# GEVCU-5_1.net
KiCad netlist of a schematic drawn in EAGLE
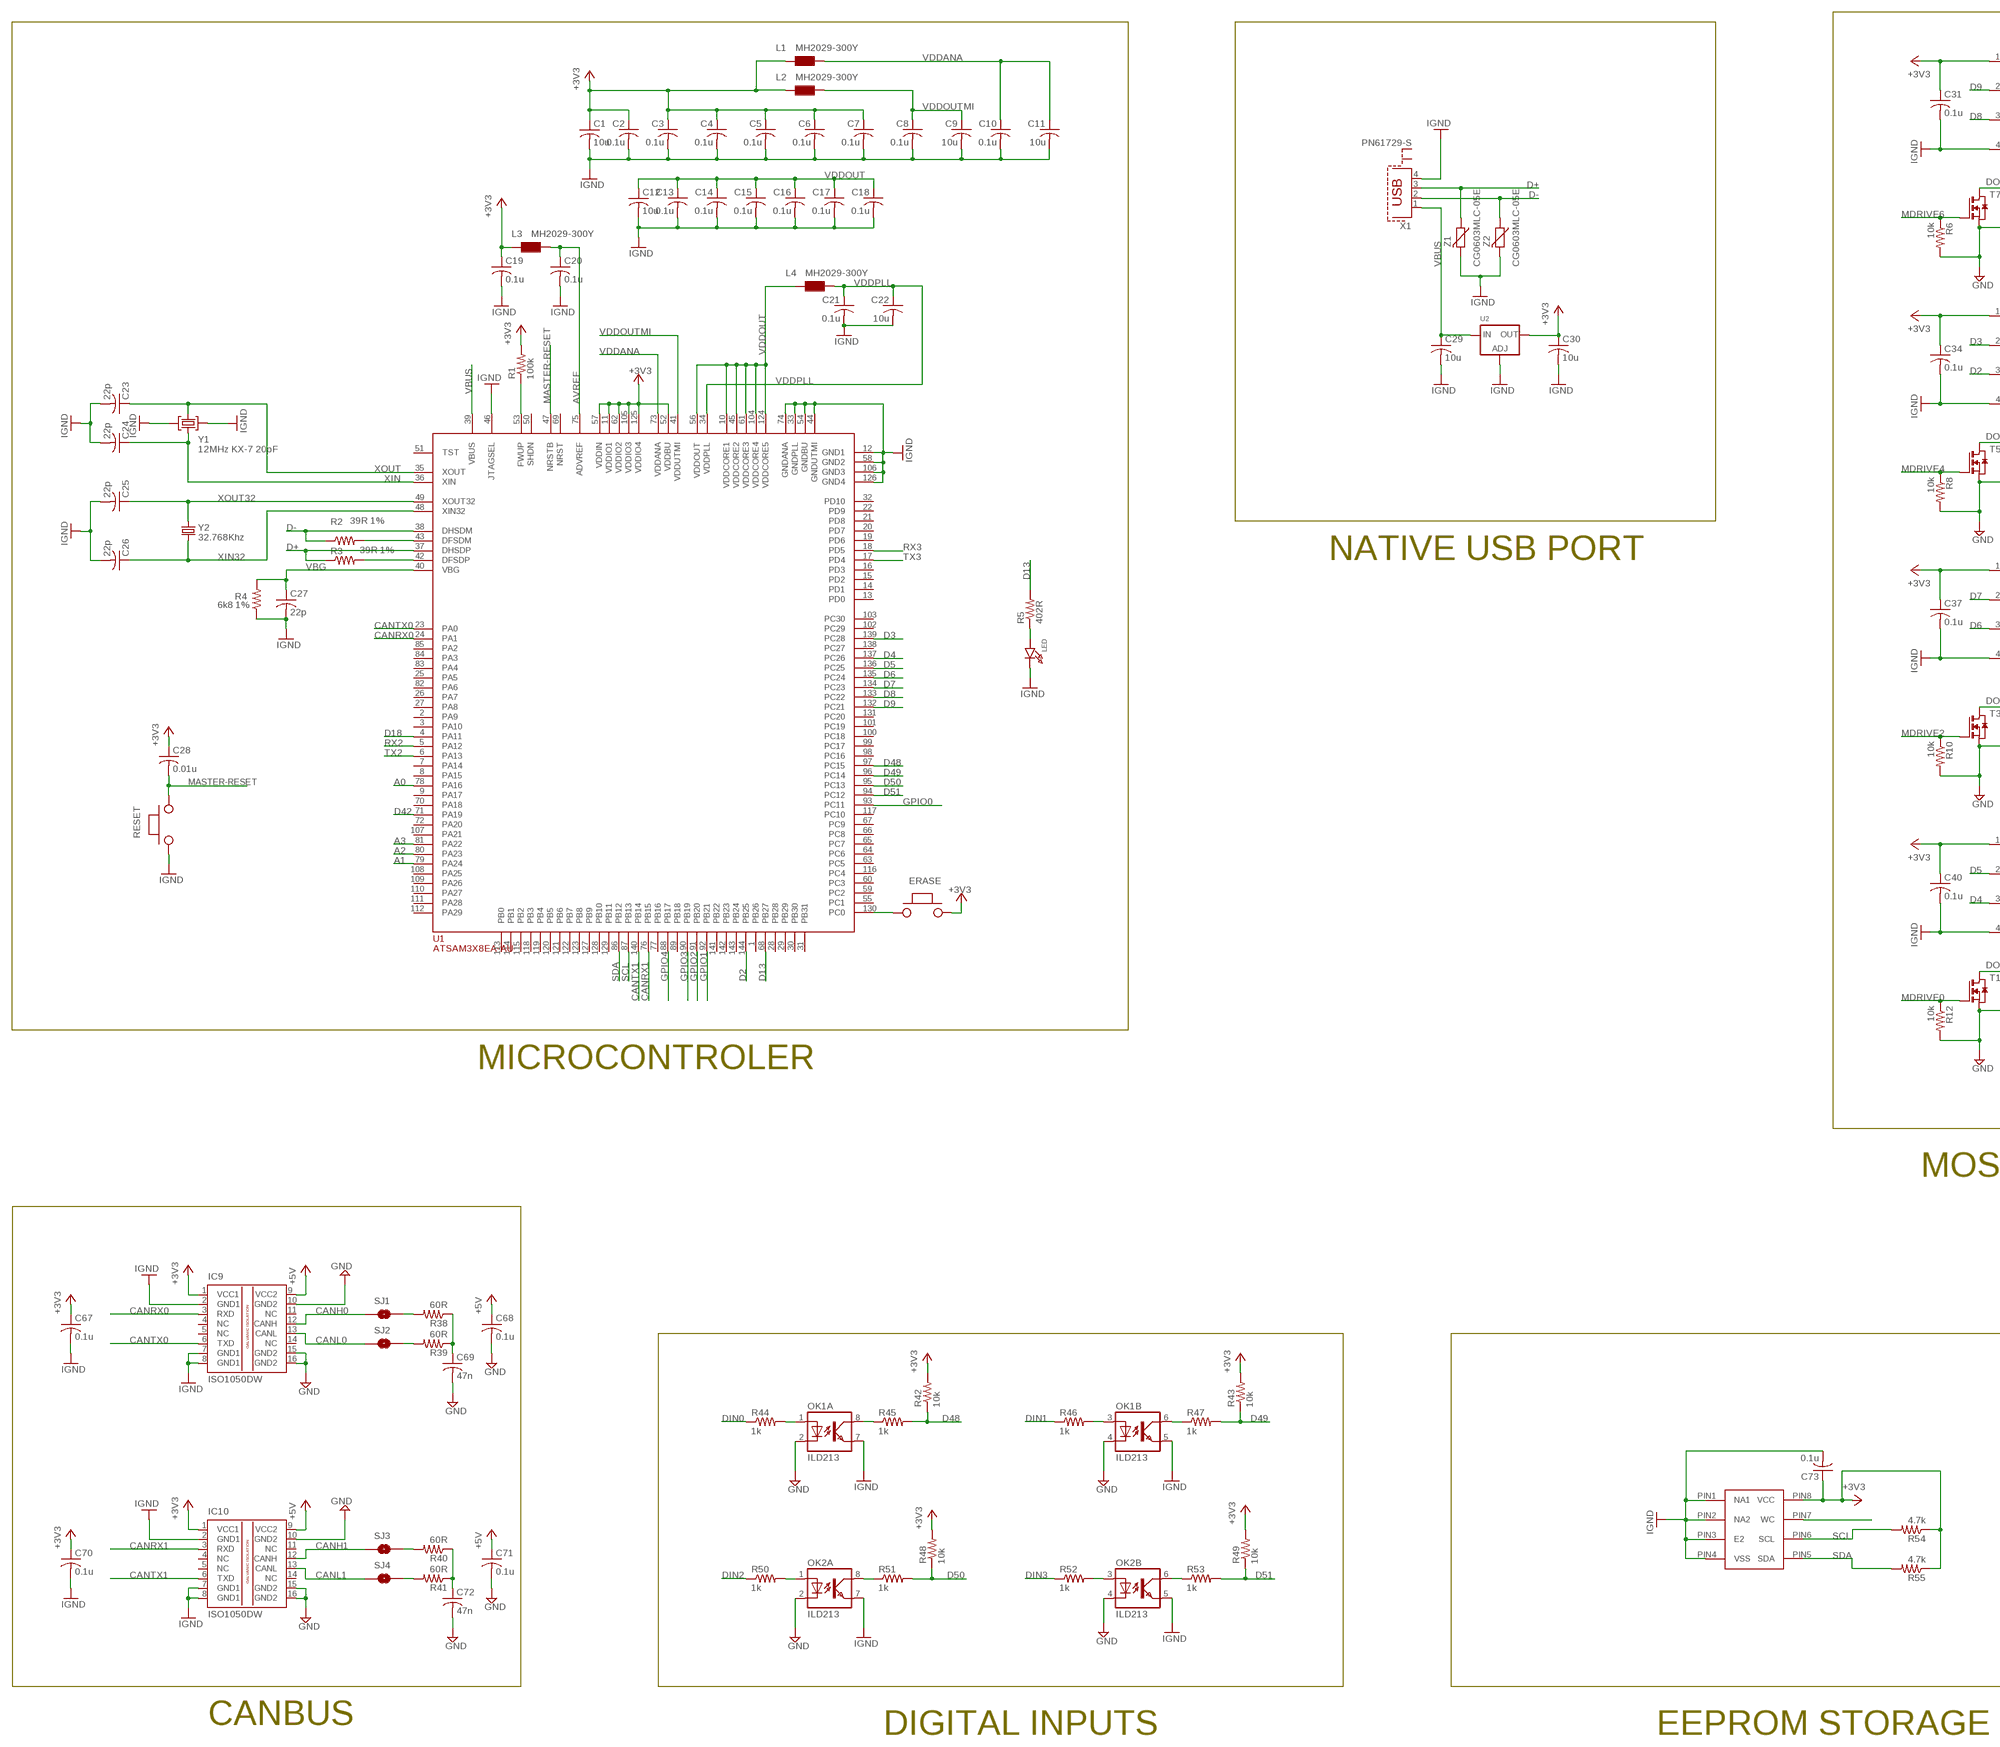
[diagram p0: schematic, sheet 1, part 1 of 2]
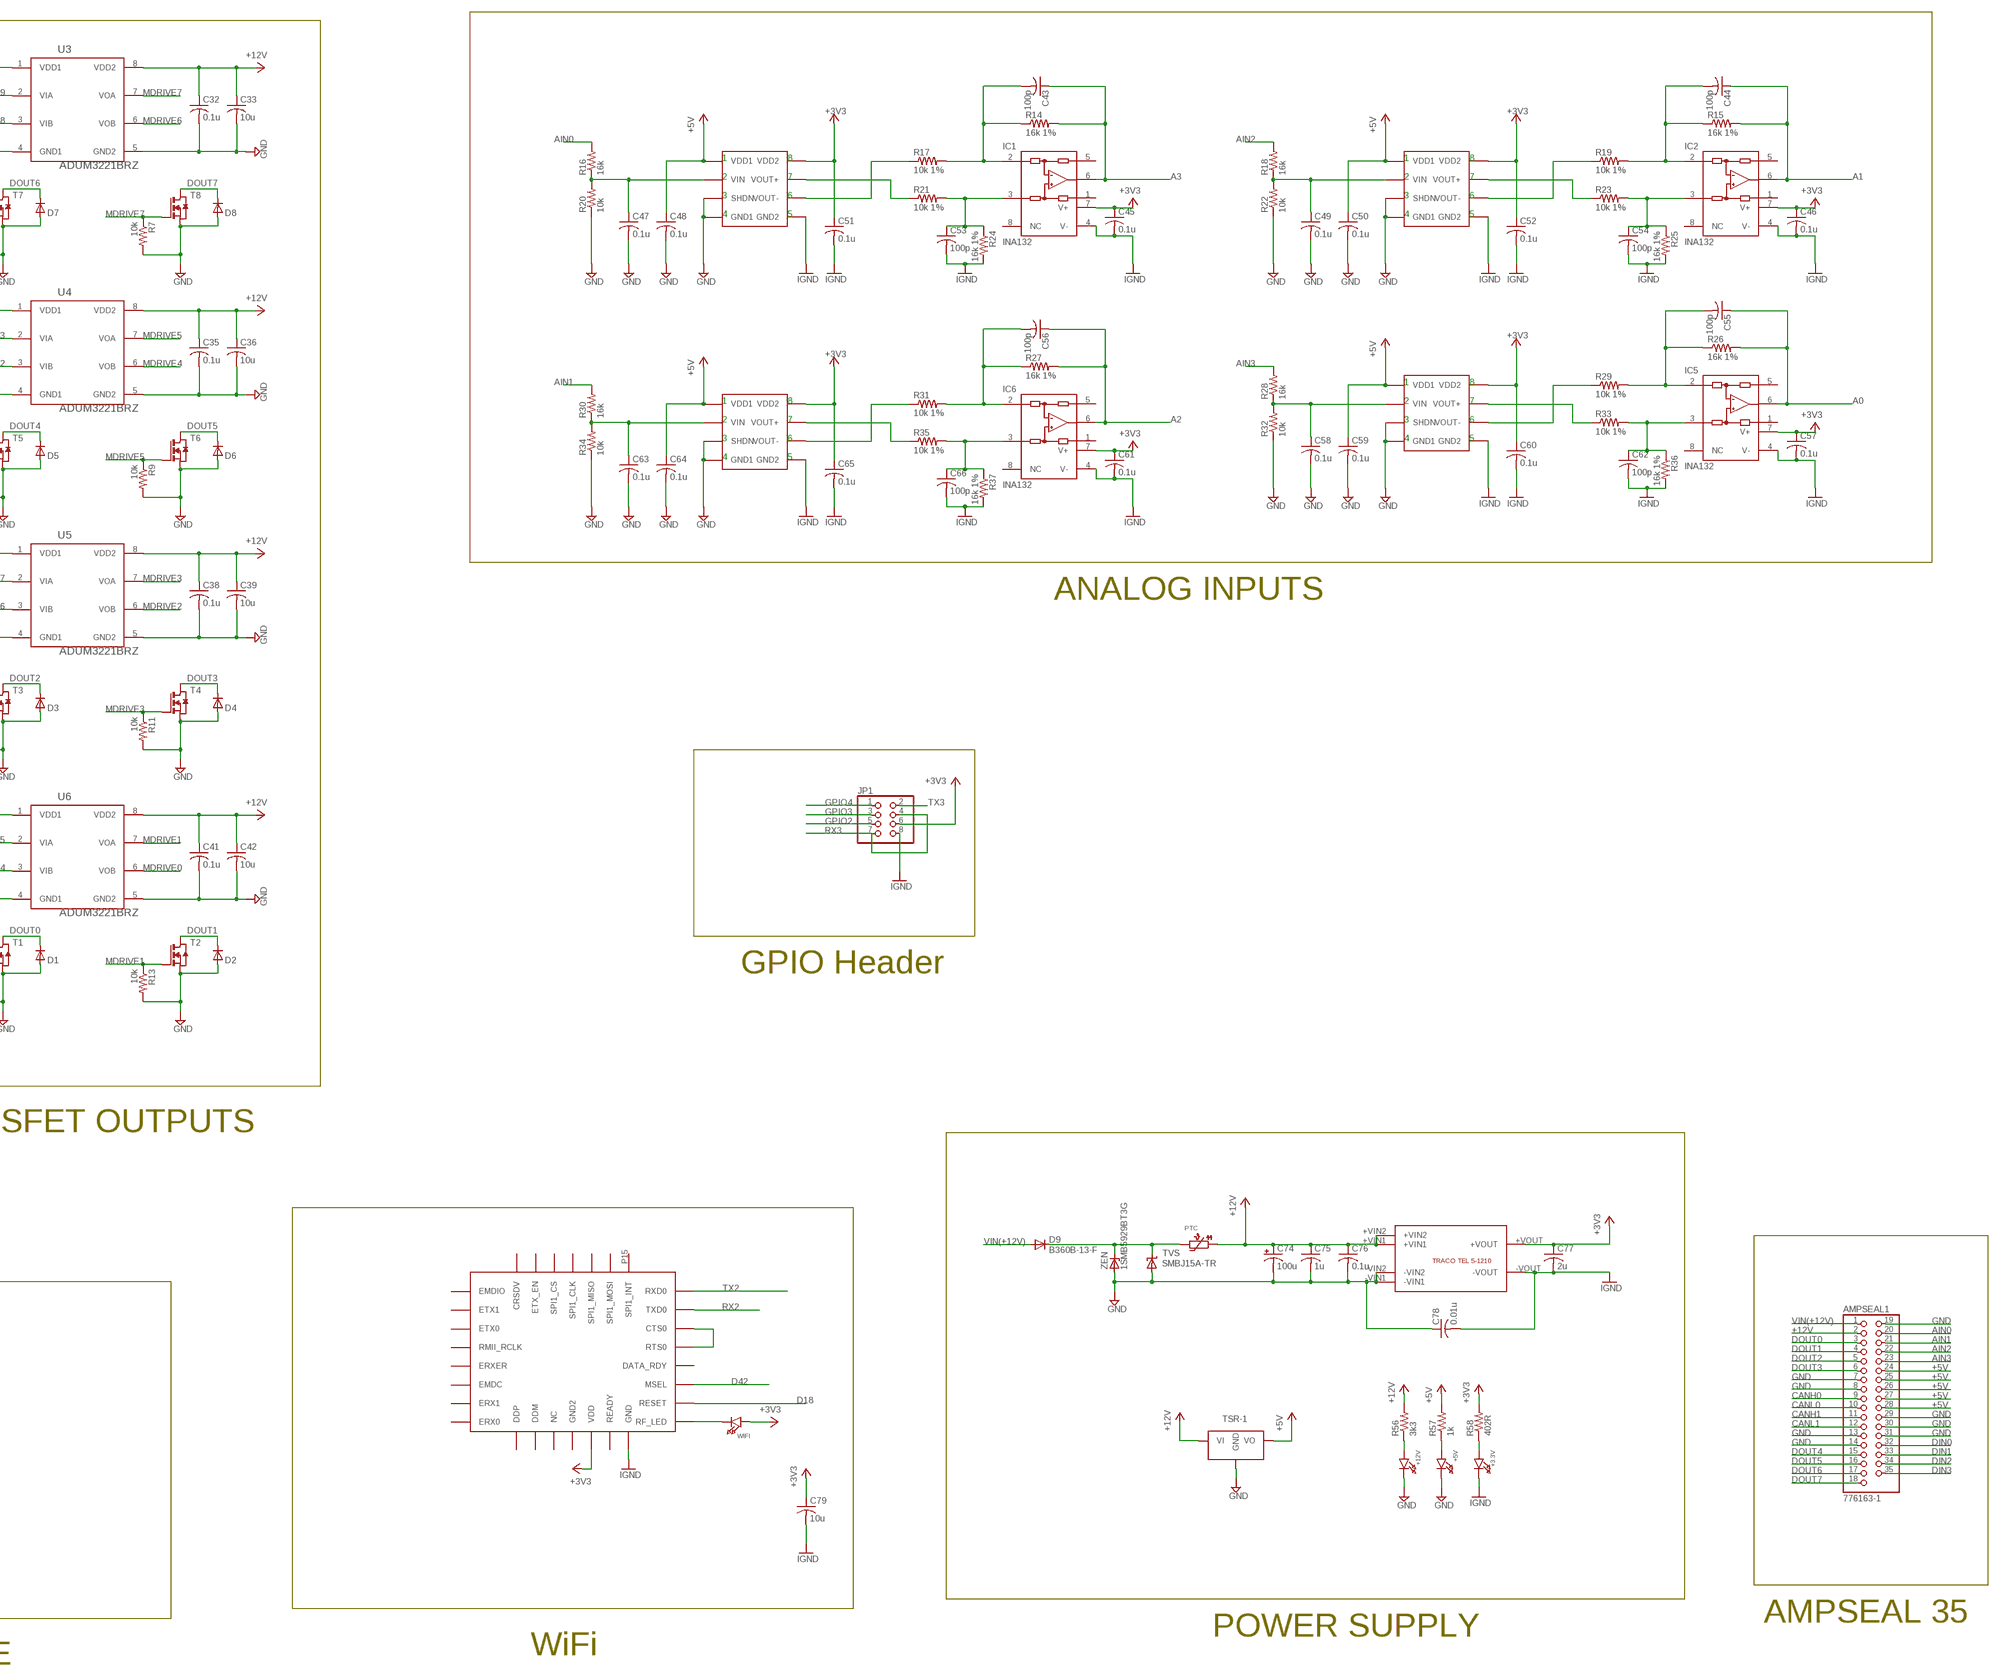
[diagram p1: schematic, sheet 1, part 2 of 2]

(export (version "E")
  (design (tool "Eeschema 10.0.6"))
  (components
    (comp (ref "+3.3V")
      (value "LED0805")
      (footprint "eagle-import:CHIPLED_0805")
      (libsource (lib "eagle-import") (part "LED0805"))
    )
    (comp (ref "+5V")
      (value "LED0805")
      (footprint "eagle-import:CHIPLED_0805")
      (libsource (lib "eagle-import") (part "LED0805"))
    )
    (comp (ref "+12V")
      (value "LED0805")
      (footprint "eagle-import:CHIPLED_0805")
      (libsource (lib "eagle-import") (part "LED0805"))
    )
    (comp (ref "AMPSEAL1")
      (value "776163-1")
      (footprint "eagle-import:AMPSEAL35")
      (libsource (lib "eagle-import") (part "AMPSEAL35"))
    )
    (comp (ref "C1")
      (value "10u")
      (footprint "eagle-import:C0805")
      (libsource (lib "eagle-import") (part "C-USC0805"))
    )
    (comp (ref "C2")
      (value "0.1u")
      (footprint "eagle-import:C0805")
      (libsource (lib "eagle-import") (part "C-USC0805"))
    )
    (comp (ref "C3")
      (value "0.1u")
      (footprint "eagle-import:C0805")
      (libsource (lib "eagle-import") (part "C-USC0805"))
    )
    (comp (ref "C4")
      (value "0.1u")
      (footprint "eagle-import:C0805")
      (libsource (lib "eagle-import") (part "C-USC0805"))
    )
    (comp (ref "C5")
      (value "0.1u")
      (footprint "eagle-import:C0805")
      (libsource (lib "eagle-import") (part "C-USC0805"))
    )
    (comp (ref "C6")
      (value "0.1u")
      (footprint "eagle-import:C0805")
      (libsource (lib "eagle-import") (part "C-USC0805"))
    )
    (comp (ref "C7")
      (value "0.1u")
      (footprint "eagle-import:C0805")
      (libsource (lib "eagle-import") (part "C-USC0805"))
    )
    (comp (ref "C8")
      (value "0.1u")
      (footprint "eagle-import:C0805")
      (libsource (lib "eagle-import") (part "C-USC0805"))
    )
    (comp (ref "C9")
      (value "10u")
      (footprint "eagle-import:C0805")
      (libsource (lib "eagle-import") (part "C-USC0805"))
    )
    (comp (ref "C10")
      (value "0.1u")
      (footprint "eagle-import:C0805")
      (libsource (lib "eagle-import") (part "C-USC0805"))
    )
    (comp (ref "C11")
      (value "10u")
      (footprint "eagle-import:C0805")
      (libsource (lib "eagle-import") (part "C-USC0805"))
    )
    (comp (ref "C12")
      (value "10u")
      (footprint "eagle-import:C0805")
      (libsource (lib "eagle-import") (part "C-USC0805"))
    )
    (comp (ref "C13")
      (value "0.1u")
      (footprint "eagle-import:C0805")
      (libsource (lib "eagle-import") (part "C-USC0805"))
    )
    (comp (ref "C14")
      (value "0.1u")
      (footprint "eagle-import:C0805")
      (libsource (lib "eagle-import") (part "C-USC0805"))
    )
    (comp (ref "C15")
      (value "0.1u")
      (footprint "eagle-import:C0805")
      (libsource (lib "eagle-import") (part "C-USC0805"))
    )
    (comp (ref "C16")
      (value "0.1u")
      (footprint "eagle-import:C0805")
      (libsource (lib "eagle-import") (part "C-USC0805"))
    )
    (comp (ref "C17")
      (value "0.1u")
      (footprint "eagle-import:C0805")
      (libsource (lib "eagle-import") (part "C-USC0805"))
    )
    (comp (ref "C18")
      (value "0.1u")
      (footprint "eagle-import:C0805")
      (libsource (lib "eagle-import") (part "C-USC0805"))
    )
    (comp (ref "C19")
      (value "0.1u")
      (footprint "eagle-import:C0805")
      (libsource (lib "eagle-import") (part "C-USC0805"))
    )
    (comp (ref "C20")
      (value "0.1u")
      (footprint "eagle-import:C0805")
      (libsource (lib "eagle-import") (part "C-USC0805"))
    )
    (comp (ref "C21")
      (value "0.1u")
      (footprint "eagle-import:C0805")
      (libsource (lib "eagle-import") (part "C-USC0805"))
    )
    (comp (ref "C22")
      (value "10u")
      (footprint "eagle-import:C0805")
      (libsource (lib "eagle-import") (part "C-USC0805"))
    )
    (comp (ref "C23")
      (value "22p")
      (footprint "eagle-import:C1206")
      (libsource (lib "eagle-import") (part "C-USC1206"))
    )
    (comp (ref "C24")
      (value "22p")
      (footprint "eagle-import:C1206")
      (libsource (lib "eagle-import") (part "C-USC1206"))
    )
    (comp (ref "C25")
      (value "22p")
      (footprint "eagle-import:C0805")
      (libsource (lib "eagle-import") (part "C-USC0805"))
    )
    (comp (ref "C26")
      (value "22p")
      (footprint "eagle-import:C0805")
      (libsource (lib "eagle-import") (part "C-USC0805"))
    )
    (comp (ref "C27")
      (value "22p")
      (footprint "eagle-import:C0805")
      (libsource (lib "eagle-import") (part "C-USC0805"))
    )
    (comp (ref "C28")
      (value "0.01u")
      (footprint "eagle-import:C0805")
      (libsource (lib "eagle-import") (part "C-USC0805"))
    )
    (comp (ref "C29")
      (value "10u")
      (footprint "eagle-import:C0805")
      (libsource (lib "eagle-import") (part "C-USC0805"))
    )
    (comp (ref "C30")
      (value "10u")
      (footprint "eagle-import:C0805")
      (libsource (lib "eagle-import") (part "C-USC0805"))
    )
    (comp (ref "C31")
      (value "0.1u")
      (footprint "eagle-import:C0805")
      (libsource (lib "eagle-import") (part "C-USC0805"))
    )
    (comp (ref "C32")
      (value "0.1u")
      (footprint "eagle-import:C0805")
      (libsource (lib "eagle-import") (part "C-USC0805"))
    )
    (comp (ref "C33")
      (value "10u")
      (footprint "eagle-import:C0805")
      (libsource (lib "eagle-import") (part "C-USC0805"))
    )
    (comp (ref "C34")
      (value "0.1u")
      (footprint "eagle-import:C0805")
      (libsource (lib "eagle-import") (part "C-USC0805"))
    )
    (comp (ref "C35")
      (value "0.1u")
      (footprint "eagle-import:C0805")
      (libsource (lib "eagle-import") (part "C-USC0805"))
    )
    (comp (ref "C36")
      (value "10u")
      (footprint "eagle-import:C0805")
      (libsource (lib "eagle-import") (part "C-USC0805"))
    )
    (comp (ref "C37")
      (value "0.1u")
      (footprint "eagle-import:C0805")
      (libsource (lib "eagle-import") (part "C-USC0805"))
    )
    (comp (ref "C38")
      (value "0.1u")
      (footprint "eagle-import:C0805")
      (libsource (lib "eagle-import") (part "C-USC0805"))
    )
    (comp (ref "C39")
      (value "10u")
      (footprint "eagle-import:C0805")
      (libsource (lib "eagle-import") (part "C-USC0805"))
    )
    (comp (ref "C40")
      (value "0.1u")
      (footprint "eagle-import:C0805")
      (libsource (lib "eagle-import") (part "C-USC0805"))
    )
    (comp (ref "C41")
      (value "0.1u")
      (footprint "eagle-import:C0805")
      (libsource (lib "eagle-import") (part "C-USC0805"))
    )
    (comp (ref "C42")
      (value "10u")
      (footprint "eagle-import:C0805")
      (libsource (lib "eagle-import") (part "C-USC0805"))
    )
    (comp (ref "C43")
      (value "100p")
      (footprint "eagle-import:C0805")
      (libsource (lib "eagle-import") (part "C-USC0805"))
    )
    (comp (ref "C44")
      (value "100p")
      (footprint "eagle-import:C0805")
      (libsource (lib "eagle-import") (part "C-USC0805"))
    )
    (comp (ref "C45")
      (value "0.1u")
      (footprint "eagle-import:C0805")
      (libsource (lib "eagle-import") (part "C-USC0805"))
    )
    (comp (ref "C46")
      (value "0.1u")
      (footprint "eagle-import:C0805")
      (libsource (lib "eagle-import") (part "C-USC0805"))
    )
    (comp (ref "C47")
      (value "0.1u")
      (footprint "eagle-import:C0805")
      (libsource (lib "eagle-import") (part "C-USC0805"))
    )
    (comp (ref "C48")
      (value "0.1u")
      (footprint "eagle-import:C1206")
      (libsource (lib "eagle-import") (part "C-USC1206"))
    )
    (comp (ref "C49")
      (value "0.1u")
      (footprint "eagle-import:C0805")
      (libsource (lib "eagle-import") (part "C-USC0805"))
    )
    (comp (ref "C50")
      (value "0.1u")
      (footprint "eagle-import:C1206")
      (libsource (lib "eagle-import") (part "C-USC1206"))
    )
    (comp (ref "C51")
      (value "0.1u")
      (footprint "eagle-import:C0805")
      (libsource (lib "eagle-import") (part "C-USC0805"))
    )
    (comp (ref "C52")
      (value "0.1u")
      (footprint "eagle-import:C0805")
      (libsource (lib "eagle-import") (part "C-USC0805"))
    )
    (comp (ref "C53")
      (value "100p")
      (footprint "eagle-import:C0805")
      (libsource (lib "eagle-import") (part "C-USC0805"))
    )
    (comp (ref "C54")
      (value "100p")
      (footprint "eagle-import:C0805")
      (libsource (lib "eagle-import") (part "C-USC0805"))
    )
    (comp (ref "C55")
      (value "100p")
      (footprint "eagle-import:C0805")
      (libsource (lib "eagle-import") (part "C-USC0805"))
    )
    (comp (ref "C56")
      (value "100p")
      (footprint "eagle-import:C0805")
      (libsource (lib "eagle-import") (part "C-USC0805"))
    )
    (comp (ref "C57")
      (value "0.1u")
      (footprint "eagle-import:C0805")
      (libsource (lib "eagle-import") (part "C-USC0805"))
    )
    (comp (ref "C58")
      (value "0.1u")
      (footprint "eagle-import:C0805")
      (libsource (lib "eagle-import") (part "C-USC0805"))
    )
    (comp (ref "C59")
      (value "0.1u")
      (footprint "eagle-import:C1206")
      (libsource (lib "eagle-import") (part "C-USC1206"))
    )
    (comp (ref "C60")
      (value "0.1u")
      (footprint "eagle-import:C0805")
      (libsource (lib "eagle-import") (part "C-USC0805"))
    )
    (comp (ref "C61")
      (value "0.1u")
      (footprint "eagle-import:C0805")
      (libsource (lib "eagle-import") (part "C-USC0805"))
    )
    (comp (ref "C62")
      (value "100p")
      (footprint "eagle-import:C0805")
      (libsource (lib "eagle-import") (part "C-USC0805"))
    )
    (comp (ref "C63")
      (value "0.1u")
      (footprint "eagle-import:C0805")
      (libsource (lib "eagle-import") (part "C-USC0805"))
    )
    (comp (ref "C64")
      (value "0.1u")
      (footprint "eagle-import:C1206")
      (libsource (lib "eagle-import") (part "C-USC1206"))
    )
    (comp (ref "C65")
      (value "0.1u")
      (footprint "eagle-import:C0805")
      (libsource (lib "eagle-import") (part "C-USC0805"))
    )
    (comp (ref "C66")
      (value "100p")
      (footprint "eagle-import:C0805")
      (libsource (lib "eagle-import") (part "C-USC0805"))
    )
    (comp (ref "C67")
      (value "0.1u")
      (footprint "eagle-import:C0805")
      (libsource (lib "eagle-import") (part "C-USC0805"))
    )
    (comp (ref "C68")
      (value "0.1u")
      (footprint "eagle-import:C0805")
      (libsource (lib "eagle-import") (part "C-USC0805"))
    )
    (comp (ref "C69")
      (value "47n")
      (footprint "eagle-import:C0805")
      (libsource (lib "eagle-import") (part "C-USC0805"))
    )
    (comp (ref "C70")
      (value "0.1u")
      (footprint "eagle-import:C0805")
      (libsource (lib "eagle-import") (part "C-USC0805"))
    )
    (comp (ref "C71")
      (value "0.1u")
      (footprint "eagle-import:C0805")
      (libsource (lib "eagle-import") (part "C-USC0805"))
    )
    (comp (ref "C72")
      (value "47n")
      (footprint "eagle-import:C0805")
      (libsource (lib "eagle-import") (part "C-USC0805"))
    )
    (comp (ref "C73")
      (value "0.1u")
      (footprint "eagle-import:C0805")
      (libsource (lib "eagle-import") (part "C-USC0805"))
    )
    (comp (ref "C74")
      (value "100u")
      (footprint "eagle-import:E2,5-6")
      (libsource (lib "eagle-import") (part "CPOL-USE2.5-6"))
    )
    (comp (ref "C75")
      (value "1u")
      (footprint "eagle-import:C0805")
      (libsource (lib "eagle-import") (part "C-USC0805"))
    )
    (comp (ref "C76")
      (value "0.1u")
      (footprint "eagle-import:C0805")
      (libsource (lib "eagle-import") (part "C-USC0805"))
    )
    (comp (ref "C77")
      (value "2u")
      (footprint "eagle-import:C0805")
      (libsource (lib "eagle-import") (part "C-USC0805"))
    )
    (comp (ref "C78")
      (value "0.01u")
      (footprint "eagle-import:C1812")
      (libsource (lib "eagle-import") (part "C-USC1812"))
    )
    (comp (ref "C79")
      (value "10u")
      (footprint "eagle-import:C0805")
      (libsource (lib "eagle-import") (part "C-USC0805"))
    )
    (comp (ref "D1")
      (value "MBR0520LT")
      (footprint "eagle-import:SOD123")
      (libsource (lib "eagle-import") (part "MBR0520LT"))
    )
    (comp (ref "D2")
      (value "MBR0520LT")
      (footprint "eagle-import:SOD123")
      (libsource (lib "eagle-import") (part "MBR0520LT"))
    )
    (comp (ref "D3")
      (value "MBR0520LT")
      (footprint "eagle-import:SOD123")
      (libsource (lib "eagle-import") (part "MBR0520LT"))
    )
    (comp (ref "D4")
      (value "MBR0520LT")
      (footprint "eagle-import:SOD123")
      (libsource (lib "eagle-import") (part "MBR0520LT"))
    )
    (comp (ref "D5")
      (value "MBR0520LT")
      (footprint "eagle-import:SOD123")
      (libsource (lib "eagle-import") (part "MBR0520LT"))
    )
    (comp (ref "D6")
      (value "MBR0520LT")
      (footprint "eagle-import:SOD123")
      (libsource (lib "eagle-import") (part "MBR0520LT"))
    )
    (comp (ref "D7")
      (value "MBR0520LT")
      (footprint "eagle-import:SOD123")
      (libsource (lib "eagle-import") (part "MBR0520LT"))
    )
    (comp (ref "D8")
      (value "MBR0520LT")
      (footprint "eagle-import:SOD123")
      (libsource (lib "eagle-import") (part "MBR0520LT"))
    )
    (comp (ref "D9")
      (value "B360B-13-F")
      (footprint "eagle-import:SMB")
      (libsource (lib "eagle-import") (part "DIODE-SMB"))
    )
    (comp (ref "ERASE")
      (value "PUCHBUTTON")
      (footprint "eagle-import:PUCHBUTTON")
      (libsource (lib "eagle-import") (part "PUCHBUTTON"))
    )
    (comp (ref "IC1")
      (value "INA132")
      (footprint "eagle-import:SO08")
      (fields (field (name "MF") "TEXAS INSTRUMENTS") (field (name "MPN") "INA105KU"))
      (libsource (lib "eagle-import") (part "INA105U"))
    )
    (comp (ref "IC2")
      (value "INA132")
      (footprint "eagle-import:SO08")
      (fields (field (name "MF") "TEXAS INSTRUMENTS") (field (name "MPN") "INA105KU"))
      (libsource (lib "eagle-import") (part "INA105U"))
    )
    (comp (ref "IC3")
      (value "CK_CUSTOM_ACPL-C87A-000E")
      (footprint "eagle-import:CK_CUSTOM_SO8-WIDE")
      (libsource (lib "eagle-import") (part "CK_CUSTOM_ACPL-C87A-000E"))
    )
    (comp (ref "IC4")
      (value "CK_CUSTOM_ACPL-C87A-000E")
      (footprint "eagle-import:CK_CUSTOM_SO8-WIDE")
      (libsource (lib "eagle-import") (part "CK_CUSTOM_ACPL-C87A-000E"))
    )
    (comp (ref "IC5")
      (value "INA132")
      (footprint "eagle-import:SO08")
      (fields (field (name "MF") "TEXAS INSTRUMENTS") (field (name "MPN") "INA105KU"))
      (libsource (lib "eagle-import") (part "INA105U"))
    )
    (comp (ref "IC6")
      (value "INA132")
      (footprint "eagle-import:SO08")
      (fields (field (name "MF") "TEXAS INSTRUMENTS") (field (name "MPN") "INA105KU"))
      (libsource (lib "eagle-import") (part "INA105U"))
    )
    (comp (ref "IC7")
      (value "CK_CUSTOM_ACPL-C87A-000E")
      (footprint "eagle-import:CK_CUSTOM_SO8-WIDE")
      (libsource (lib "eagle-import") (part "CK_CUSTOM_ACPL-C87A-000E"))
    )
    (comp (ref "IC8")
      (value "CK_CUSTOM_ACPL-C87A-000E")
      (footprint "eagle-import:CK_CUSTOM_SO8-WIDE")
      (libsource (lib "eagle-import") (part "CK_CUSTOM_ACPL-C87A-000E"))
    )
    (comp (ref "IC9")
      (value "ISO1050DW")
      (footprint "eagle-import:DUB-R-PDSO-G8")
      (libsource (lib "eagle-import") (part "ISO1050DUB"))
    )
    (comp (ref "IC10")
      (value "ISO1050DW")
      (footprint "eagle-import:DUB-R-PDSO-G8")
      (libsource (lib "eagle-import") (part "ISO1050DUB"))
    )
    (comp (ref "JP1")
      (value "PINHD-2X4")
      (footprint "eagle-import:2X04")
      (libsource (lib "eagle-import") (part "PINHD-2X4"))
    )
    (comp (ref "L1")
      (value "MH2029-300Y")
      (footprint "eagle-import:0805")
      (libsource (lib "eagle-import") (part "WE-CBF_0805"))
    )
    (comp (ref "L2")
      (value "MH2029-300Y")
      (footprint "eagle-import:0805")
      (libsource (lib "eagle-import") (part "WE-CBF_0805"))
    )
    (comp (ref "L3")
      (value "MH2029-300Y")
      (footprint "eagle-import:0805")
      (libsource (lib "eagle-import") (part "WE-CBF_0805"))
    )
    (comp (ref "L4")
      (value "MH2029-300Y")
      (footprint "eagle-import:0805")
      (libsource (lib "eagle-import") (part "WE-CBF_0805"))
    )
    (comp (ref "LED")
      (value "LED0805")
      (footprint "eagle-import:CHIPLED_0805")
      (libsource (lib "eagle-import") (part "LED0805"))
    )
    (comp (ref "OK1")
      (value "ILD213")
      (footprint "eagle-import:SOIC08")
      (fields (field (name "MF") "VISHAY/TELEFUNKEN") (field (name "MPN") "ILD213T"))
      (libsource (lib "eagle-import") (part "ILD213"))
    )
    (comp (ref "OK2")
      (value "ILD213")
      (footprint "eagle-import:SOIC08")
      (fields (field (name "MF") "VISHAY/TELEFUNKEN") (field (name "MPN") "ILD213T"))
      (libsource (lib "eagle-import") (part "ILD213"))
    )
    (comp (ref "PTC")
      (value "PTC1812")
      (footprint "eagle-import:PTC1812")
      (libsource (lib "eagle-import") (part "PTC1812"))
    )
    (comp (ref "R1")
      (value "100k")
      (footprint "eagle-import:R0805")
      (libsource (lib "eagle-import") (part "R-US_R0805"))
    )
    (comp (ref "R2")
      (value "39R 1%")
      (footprint "eagle-import:R0805")
      (libsource (lib "eagle-import") (part "R-US_R0805"))
    )
    (comp (ref "R3")
      (value "39R 1%")
      (footprint "eagle-import:R0805")
      (libsource (lib "eagle-import") (part "R-US_R0805"))
    )
    (comp (ref "R4")
      (value "6k8 1%")
      (footprint "eagle-import:R0805")
      (libsource (lib "eagle-import") (part "R-US_R0805"))
    )
    (comp (ref "R5")
      (value "402R")
      (footprint "eagle-import:R0805")
      (libsource (lib "eagle-import") (part "R-US_R0805"))
    )
    (comp (ref "R6")
      (value "10k")
      (footprint "eagle-import:R0805")
      (libsource (lib "eagle-import") (part "R-US_R0805"))
    )
    (comp (ref "R7")
      (value "10k")
      (footprint "eagle-import:R0805")
      (libsource (lib "eagle-import") (part "R-US_R0805"))
    )
    (comp (ref "R8")
      (value "10k")
      (footprint "eagle-import:R0805")
      (libsource (lib "eagle-import") (part "R-US_R0805"))
    )
    (comp (ref "R9")
      (value "10k")
      (footprint "eagle-import:R0805")
      (libsource (lib "eagle-import") (part "R-US_R0805"))
    )
    (comp (ref "R10")
      (value "10k")
      (footprint "eagle-import:R0805")
      (libsource (lib "eagle-import") (part "R-US_R0805"))
    )
    (comp (ref "R11")
      (value "10k")
      (footprint "eagle-import:R0805")
      (libsource (lib "eagle-import") (part "R-US_R0805"))
    )
    (comp (ref "R12")
      (value "10k")
      (footprint "eagle-import:R0805")
      (libsource (lib "eagle-import") (part "R-US_R0805"))
    )
    (comp (ref "R13")
      (value "10k")
      (footprint "eagle-import:R0805")
      (libsource (lib "eagle-import") (part "R-US_R0805"))
    )
    (comp (ref "R14")
      (value "16k 1%")
      (footprint "eagle-import:R0805")
      (libsource (lib "eagle-import") (part "R-US_R0805"))
    )
    (comp (ref "R15")
      (value "16k 1%")
      (footprint "eagle-import:R0805")
      (libsource (lib "eagle-import") (part "R-US_R0805"))
    )
    (comp (ref "R16")
      (value "16k")
      (footprint "eagle-import:R0805")
      (libsource (lib "eagle-import") (part "R-US_R0805"))
    )
    (comp (ref "R17")
      (value "10k 1%")
      (footprint "eagle-import:R0805")
      (libsource (lib "eagle-import") (part "R-US_R0805"))
    )
    (comp (ref "R18")
      (value "16k")
      (footprint "eagle-import:R0805")
      (libsource (lib "eagle-import") (part "R-US_R0805"))
    )
    (comp (ref "R19")
      (value "10k 1%")
      (footprint "eagle-import:R0805")
      (libsource (lib "eagle-import") (part "R-US_R0805"))
    )
    (comp (ref "R20")
      (value "10k")
      (footprint "eagle-import:R0805")
      (libsource (lib "eagle-import") (part "R-US_R0805"))
    )
    (comp (ref "R21")
      (value "10k 1%")
      (footprint "eagle-import:R0805")
      (libsource (lib "eagle-import") (part "R-US_R0805"))
    )
    (comp (ref "R22")
      (value "10k")
      (footprint "eagle-import:R0805")
      (libsource (lib "eagle-import") (part "R-US_R0805"))
    )
    (comp (ref "R23")
      (value "10k 1%")
      (footprint "eagle-import:R0805")
      (libsource (lib "eagle-import") (part "R-US_R0805"))
    )
    (comp (ref "R24")
      (value "16k 1%")
      (footprint "eagle-import:R0805")
      (libsource (lib "eagle-import") (part "R-US_R0805"))
    )
    (comp (ref "R25")
      (value "16k 1%")
      (footprint "eagle-import:R0805")
      (libsource (lib "eagle-import") (part "R-US_R0805"))
    )
    (comp (ref "R26")
      (value "16k 1%")
      (footprint "eagle-import:R0805")
      (libsource (lib "eagle-import") (part "R-US_R0805"))
    )
    (comp (ref "R27")
      (value "16k 1%")
      (footprint "eagle-import:R0805")
      (libsource (lib "eagle-import") (part "R-US_R0805"))
    )
    (comp (ref "R28")
      (value "16k")
      (footprint "eagle-import:R0805")
      (libsource (lib "eagle-import") (part "R-US_R0805"))
    )
    (comp (ref "R29")
      (value "10k 1%")
      (footprint "eagle-import:R0805")
      (libsource (lib "eagle-import") (part "R-US_R0805"))
    )
    (comp (ref "R30")
      (value "16k")
      (footprint "eagle-import:R0805")
      (libsource (lib "eagle-import") (part "R-US_R0805"))
    )
    (comp (ref "R31")
      (value "10k 1%")
      (footprint "eagle-import:R0805")
      (libsource (lib "eagle-import") (part "R-US_R0805"))
    )
    (comp (ref "R32")
      (value "10k")
      (footprint "eagle-import:R0805")
      (libsource (lib "eagle-import") (part "R-US_R0805"))
    )
    (comp (ref "R33")
      (value "10k 1%")
      (footprint "eagle-import:R0805")
      (libsource (lib "eagle-import") (part "R-US_R0805"))
    )
    (comp (ref "R34")
      (value "10k")
      (footprint "eagle-import:R0805")
      (libsource (lib "eagle-import") (part "R-US_R0805"))
    )
    (comp (ref "R35")
      (value "10k 1%")
      (footprint "eagle-import:R0805")
      (libsource (lib "eagle-import") (part "R-US_R0805"))
    )
    (comp (ref "R36")
      (value "16k 1%")
      (footprint "eagle-import:R0805")
      (libsource (lib "eagle-import") (part "R-US_R0805"))
    )
    (comp (ref "R37")
      (value "16k 1%")
      (footprint "eagle-import:R0805")
      (libsource (lib "eagle-import") (part "R-US_R0805"))
    )
    (comp (ref "R38")
      (value "60R")
      (footprint "eagle-import:R0805")
      (libsource (lib "eagle-import") (part "R-US_R0805"))
    )
    (comp (ref "R39")
      (value "60R")
      (footprint "eagle-import:R0805")
      (libsource (lib "eagle-import") (part "R-US_R0805"))
    )
    (comp (ref "R40")
      (value "60R")
      (footprint "eagle-import:R0805")
      (libsource (lib "eagle-import") (part "R-US_R0805"))
    )
    (comp (ref "R41")
      (value "60R")
      (footprint "eagle-import:R0805")
      (libsource (lib "eagle-import") (part "R-US_R0805"))
    )
    (comp (ref "R42")
      (value "10k")
      (footprint "eagle-import:R0805")
      (libsource (lib "eagle-import") (part "R-US_R0805"))
    )
    (comp (ref "R43")
      (value "10k")
      (footprint "eagle-import:R0805")
      (libsource (lib "eagle-import") (part "R-US_R0805"))
    )
    (comp (ref "R44")
      (value "1k")
      (footprint "eagle-import:R0805")
      (libsource (lib "eagle-import") (part "R-US_R0805"))
    )
    (comp (ref "R45")
      (value "1k")
      (footprint "eagle-import:R0805")
      (libsource (lib "eagle-import") (part "R-US_R0805"))
    )
    (comp (ref "R46")
      (value "1k")
      (footprint "eagle-import:R0805")
      (libsource (lib "eagle-import") (part "R-US_R0805"))
    )
    (comp (ref "R47")
      (value "1k")
      (footprint "eagle-import:R0805")
      (libsource (lib "eagle-import") (part "R-US_R0805"))
    )
    (comp (ref "R48")
      (value "10k")
      (footprint "eagle-import:R0805")
      (libsource (lib "eagle-import") (part "R-US_R0805"))
    )
    (comp (ref "R49")
      (value "10k")
      (footprint "eagle-import:R0805")
      (libsource (lib "eagle-import") (part "R-US_R0805"))
    )
    (comp (ref "R50")
      (value "1k")
      (footprint "eagle-import:R0805")
      (libsource (lib "eagle-import") (part "R-US_R0805"))
    )
    (comp (ref "R51")
      (value "1k")
      (footprint "eagle-import:R0805")
      (libsource (lib "eagle-import") (part "R-US_R0805"))
    )
    (comp (ref "R52")
      (value "1k")
      (footprint "eagle-import:R0805")
      (libsource (lib "eagle-import") (part "R-US_R0805"))
    )
    (comp (ref "R53")
      (value "1k")
      (footprint "eagle-import:R0805")
      (libsource (lib "eagle-import") (part "R-US_R0805"))
    )
    (comp (ref "R54")
      (value "4.7k")
      (footprint "eagle-import:R0805")
      (libsource (lib "eagle-import") (part "R-US_R0805"))
    )
    (comp (ref "R55")
      (value "4.7k")
      (footprint "eagle-import:R0805")
      (libsource (lib "eagle-import") (part "R-US_R0805"))
    )
    (comp (ref "R56")
      (value "3k3")
      (footprint "eagle-import:R0805")
      (libsource (lib "eagle-import") (part "R-US_R0805"))
    )
    (comp (ref "R57")
      (value "1k")
      (footprint "eagle-import:R0805")
      (libsource (lib "eagle-import") (part "R-US_R0805"))
    )
    (comp (ref "R58")
      (value "402R")
      (footprint "eagle-import:R0805")
      (libsource (lib "eagle-import") (part "R-US_R0805"))
    )
    (comp (ref "RESET")
      (value "PUCHBUTTON")
      (footprint "eagle-import:PUCHBUTTON")
      (libsource (lib "eagle-import") (part "PUCHBUTTON"))
    )
    (comp (ref "SJ1")
      (value "SOLDERJUMPERNO")
      (footprint "eagle-import:SJ_2S-NO")
      (libsource (lib "eagle-import") (part "SOLDERJUMPERNO"))
    )
    (comp (ref "SJ2")
      (value "SOLDERJUMPERNO")
      (footprint "eagle-import:SJ_2S-NO")
      (libsource (lib "eagle-import") (part "SOLDERJUMPERNO"))
    )
    (comp (ref "SJ3")
      (value "SOLDERJUMPERNO")
      (footprint "eagle-import:SJ_2S-NO")
      (libsource (lib "eagle-import") (part "SOLDERJUMPERNO"))
    )
    (comp (ref "SJ4")
      (value "SOLDERJUMPERNO")
      (footprint "eagle-import:SJ_2S-NO")
      (libsource (lib "eagle-import") (part "SOLDERJUMPERNO"))
    )
    (comp (ref "T1")
      (value "NMOSSOT223")
      (footprint "eagle-import:SOT223")
      (libsource (lib "eagle-import") (part "NMOSSOT223"))
    )
    (comp (ref "T2")
      (value "NMOSSOT223")
      (footprint "eagle-import:SOT223")
      (libsource (lib "eagle-import") (part "NMOSSOT223"))
    )
    (comp (ref "T3")
      (value "NMOSSOT223")
      (footprint "eagle-import:SOT223")
      (libsource (lib "eagle-import") (part "NMOSSOT223"))
    )
    (comp (ref "T4")
      (value "NMOSSOT223")
      (footprint "eagle-import:SOT223")
      (libsource (lib "eagle-import") (part "NMOSSOT223"))
    )
    (comp (ref "T5")
      (value "NMOSSOT223")
      (footprint "eagle-import:SOT223")
      (libsource (lib "eagle-import") (part "NMOSSOT223"))
    )
    (comp (ref "T6")
      (value "NMOSSOT223")
      (footprint "eagle-import:SOT223")
      (libsource (lib "eagle-import") (part "NMOSSOT223"))
    )
    (comp (ref "T7")
      (value "NMOSSOT223")
      (footprint "eagle-import:SOT223")
      (libsource (lib "eagle-import") (part "NMOSSOT223"))
    )
    (comp (ref "T8")
      (value "NMOSSOT223")
      (footprint "eagle-import:SOT223")
      (libsource (lib "eagle-import") (part "NMOSSOT223"))
    )
    (comp (ref "TVS")
      (value "SMBJ15A-TR")
      (footprint "eagle-import:SMBJ")
      (libsource (lib "eagle-import") (part "SUPPRESSOR-SMBJ"))
    )
    (comp (ref "U$1")
      (value "NANOREACH")
      (footprint "eagle-import:NANOREACH")
      (libsource (lib "eagle-import") (part "NANOREACH"))
    )
    (comp (ref "U1")
      (value "ATSAM3X8EA-AU")
      (footprint "eagle-import:LQFP144")
      (libsource (lib "eagle-import") (part "ATSAM3X/AAU"))
    )
    (comp (ref "U2")
      (value "LM1117SOT223-WAVE")
      (footprint "eagle-import:SOT223-W")
      (libsource (lib "eagle-import") (part "LM1117SOT223-WAVE"))
    )
    (comp (ref "U3")
      (value "ADUM3221BRZ")
      (footprint "eagle-import:SOIC127P600X175-8N")
      (libsource (lib "eagle-import") (part "ADUM3221BRZ"))
    )
    (comp (ref "U4")
      (value "ADUM3221BRZ")
      (footprint "eagle-import:SOIC127P600X175-8N")
      (libsource (lib "eagle-import") (part "ADUM3221BRZ"))
    )
    (comp (ref "U5")
      (value "ADUM3221BRZ")
      (footprint "eagle-import:SOIC127P600X175-8N")
      (libsource (lib "eagle-import") (part "ADUM3221BRZ"))
    )
    (comp (ref "U6")
      (value "ADUM3221BRZ")
      (footprint "eagle-import:SOIC127P600X175-8N")
      (libsource (lib "eagle-import") (part "ADUM3221BRZ"))
    )
    (comp (ref "U7")
      (value "CK_CUSTOM_M24M02-DRMN6TP")
      (footprint "eagle-import:CK_CUSTOM_SOIC8")
      (libsource (lib "eagle-import") (part "CK_CUSTOM_M24M02-DRMN6TP"))
    )
    (comp (ref "U8")
      (value "TRACO")
      (footprint "eagle-import:TRACO")
      (libsource (lib "eagle-import") (part "TRACO"))
    )
    (comp (ref "U9")
      (value "TSR-1")
      (footprint "eagle-import:TSR-1")
      (libsource (lib "eagle-import") (part "TSR-1"))
    )
    (comp (ref "WIFI")
      (value "LED0805")
      (footprint "eagle-import:CHIPLED_0805")
      (libsource (lib "eagle-import") (part "LED0805"))
    )
    (comp (ref "X1")
      (value "PN61729-S")
      (footprint "eagle-import:PN61729-S")
      (libsource (lib "eagle-import") (part "PN61729-S"))
    )
    (comp (ref "Y1")
      (value "12MHz KX-7 20pF")
      (footprint "eagle-import:CRYSTAL-3.2-2.5")
      (libsource (lib "eagle-import") (part "CRYSTAL-3.2-2.5"))
    )
    (comp (ref "Y2")
      (value "32.768Khz")
      (footprint "eagle-import:ARDUINO_WIFI_SHIELD_V018_TG_RESONATOR_EPSON_FC_145")
      (libsource (lib "eagle-import") (part "ARDUINO_WIFI_SHIELD_V018_TG_RESONATOR_EPSON_FC_145"))
    )
    (comp (ref "Z1")
      (value "CG0603MLC-05E")
      (footprint "eagle-import:CT_CN0603")
      (libsource (lib "eagle-import") (part "VARISTORCN0603"))
    )
    (comp (ref "Z2")
      (value "CG0603MLC-05E")
      (footprint "eagle-import:CT_CN0603")
      (libsource (lib "eagle-import") (part "VARISTORCN0603"))
    )
    (comp (ref "ZEN")
      (value "1SMB5929BT3G")
      (footprint "eagle-import:SMB")
      (libsource (lib "eagle-import") (part "ZENER-DIODESMB"))
    )
  )
  (nets
    (net (code "1") (name "+3V3") (class "Default")
      (node (ref "C1") (pin "1") (pinfunction "1_1") (pintype "passive"))
      (node (ref "C19") (pin "1") (pinfunction "1_1") (pintype "passive"))
      (node (ref "C2") (pin "1") (pinfunction "1_1") (pintype "passive"))
      (node (ref "C28") (pin "1") (pinfunction "1_1") (pintype "passive"))
      (node (ref "C3") (pin "1") (pinfunction "1_1") (pintype "passive"))
      (node (ref "C30") (pin "1") (pinfunction "1_1") (pintype "passive"))
      (node (ref "C31") (pin "1") (pinfunction "1_1") (pintype "passive"))
      (node (ref "C34") (pin "1") (pinfunction "1_1") (pintype "passive"))
      (node (ref "C37") (pin "1") (pinfunction "1_1") (pintype "passive"))
      (node (ref "C4") (pin "1") (pinfunction "1_1") (pintype "passive"))
      (node (ref "C40") (pin "1") (pinfunction "1_1") (pintype "passive"))
      (node (ref "C45") (pin "1") (pinfunction "1_1") (pintype "passive"))
      (node (ref "C46") (pin "1") (pinfunction "1_1") (pintype "passive"))
      (node (ref "C5") (pin "1") (pinfunction "1_1") (pintype "passive"))
      (node (ref "C51") (pin "1") (pinfunction "1_1") (pintype "passive"))
      (node (ref "C52") (pin "1") (pinfunction "1_1") (pintype "passive"))
      (node (ref "C57") (pin "1") (pinfunction "1_1") (pintype "passive"))
      (node (ref "C6") (pin "1") (pinfunction "1_1") (pintype "passive"))
      (node (ref "C60") (pin "1") (pinfunction "1_1") (pintype "passive"))
      (node (ref "C61") (pin "1") (pinfunction "1_1") (pintype "passive"))
      (node (ref "C65") (pin "1") (pinfunction "1_1") (pintype "passive"))
      (node (ref "C67") (pin "1") (pinfunction "1_1") (pintype "passive"))
      (node (ref "C7") (pin "1") (pinfunction "1_1") (pintype "passive"))
      (node (ref "C70") (pin "1") (pinfunction "1_1") (pintype "passive"))
      (node (ref "C73") (pin "1") (pinfunction "1_1") (pintype "passive"))
      (node (ref "C77") (pin "1") (pinfunction "1_1") (pintype "passive"))
      (node (ref "C79") (pin "1") (pinfunction "1_1") (pintype "passive"))
      (node (ref "ERASE") (pin "P$2") (pinfunction "P$5_P$2") (pintype "bidirectional"))
      (node (ref "IC1") (pin "7") (pinfunction "V+_7") (pintype "power_in"))
      (node (ref "IC10") (pin "1") (pinfunction "VCC1_1") (pintype "input"))
      (node (ref "IC2") (pin "7") (pinfunction "V+_7") (pintype "power_in"))
      (node (ref "IC3") (pin "8") (pinfunction "VDD2_8") (pintype "bidirectional"))
      (node (ref "IC4") (pin "8") (pinfunction "VDD2_8") (pintype "bidirectional"))
      (node (ref "IC5") (pin "7") (pinfunction "V+_7") (pintype "power_in"))
      (node (ref "IC6") (pin "7") (pinfunction "V+_7") (pintype "power_in"))
      (node (ref "IC7") (pin "8") (pinfunction "VDD2_8") (pintype "bidirectional"))
      (node (ref "IC8") (pin "8") (pinfunction "VDD2_8") (pintype "bidirectional"))
      (node (ref "IC9") (pin "1") (pinfunction "VCC1_1") (pintype "input"))
      (node (ref "JP1") (pin "6") (pinfunction "6_6") (pintype "passive"))
      (node (ref "L1") (pin "1") (pinfunction "1_1") (pintype "passive"))
      (node (ref "L2") (pin "1") (pinfunction "1_1") (pintype "passive"))
      (node (ref "L3") (pin "1") (pinfunction "1_1") (pintype "passive"))
      (node (ref "R1") (pin "2") (pinfunction "2_2") (pintype "passive"))
      (node (ref "R42") (pin "2") (pinfunction "2_2") (pintype "passive"))
      (node (ref "R43") (pin "2") (pinfunction "2_2") (pintype "passive"))
      (node (ref "R48") (pin "2") (pinfunction "2_2") (pintype "passive"))
      (node (ref "R49") (pin "2") (pinfunction "2_2") (pintype "passive"))
      (node (ref "R54") (pin "1") (pinfunction "1_1") (pintype "passive"))
      (node (ref "R55") (pin "1") (pinfunction "1_1") (pintype "passive"))
      (node (ref "R58") (pin "2") (pinfunction "2_2") (pintype "passive"))
      (node (ref "U$1") (pin "P1") (pinfunction "VDD_P1") (pintype "bidirectional"))
      (node (ref "U1") (pin "105") (pinfunction "VDDIO3_105") (pintype "power_in"))
      (node (ref "U1") (pin "11") (pinfunction "VDDIO1_11") (pintype "power_in"))
      (node (ref "U1") (pin "125") (pinfunction "VDDIO4_125") (pintype "power_in"))
      (node (ref "U1") (pin "52") (pinfunction "VDDBU_52") (pintype "power_in"))
      (node (ref "U1") (pin "57") (pinfunction "VDDIN_57") (pintype "power_in"))
      (node (ref "U1") (pin "62") (pinfunction "VDDIO2_62") (pintype "power_in"))
      (node (ref "U2") (pin "2") (pinfunction "OUT_2") (pintype "passive"))
      (node (ref "U3") (pin "1") (pinfunction "VDD1_1") (pintype "power_in"))
      (node (ref "U4") (pin "1") (pinfunction "VDD1_1") (pintype "power_in"))
      (node (ref "U5") (pin "1") (pinfunction "VDD1_1") (pintype "power_in"))
      (node (ref "U6") (pin "1") (pinfunction "VDD1_1") (pintype "power_in"))
      (node (ref "U7") (pin "PIN8") (pinfunction "VCC_PIN8") (pintype "bidirectional"))
      (node (ref "U8") (pin "+VOUT") (pinfunction "+VOUT_+VOUT") (pintype "bidirectional"))
      (node (ref "WIFI") (pin "A") (pinfunction "A_A") (pintype "passive"))
    )
    (net (code "2") (name "+5V") (class "Default")
      (node (ref "AMPSEAL1") (pin "24") (pinfunction "24_24") (pintype "passive"))
      (node (ref "AMPSEAL1") (pin "25") (pinfunction "25_25") (pintype "passive"))
      (node (ref "AMPSEAL1") (pin "26") (pinfunction "26_26") (pintype "passive"))
      (node (ref "AMPSEAL1") (pin "27") (pinfunction "27_27") (pintype "passive"))
      (node (ref "AMPSEAL1") (pin "28") (pinfunction "28_28") (pintype "passive"))
      (node (ref "C48") (pin "1") (pinfunction "1_1") (pintype "passive"))
      (node (ref "C50") (pin "1") (pinfunction "1_1") (pintype "passive"))
      (node (ref "C59") (pin "1") (pinfunction "1_1") (pintype "passive"))
      (node (ref "C64") (pin "1") (pinfunction "1_1") (pintype "passive"))
      (node (ref "C68") (pin "1") (pinfunction "1_1") (pintype "passive"))
      (node (ref "C71") (pin "1") (pinfunction "1_1") (pintype "passive"))
      (node (ref "IC10") (pin "9") (pinfunction "VCC2_9") (pintype "input"))
      (node (ref "IC3") (pin "1") (pinfunction "VDD1_1") (pintype "bidirectional"))
      (node (ref "IC4") (pin "1") (pinfunction "VDD1_1") (pintype "bidirectional"))
      (node (ref "IC7") (pin "1") (pinfunction "VDD1_1") (pintype "bidirectional"))
      (node (ref "IC8") (pin "1") (pinfunction "VDD1_1") (pintype "bidirectional"))
      (node (ref "IC9") (pin "9") (pinfunction "VCC2_9") (pintype "input"))
      (node (ref "R57") (pin "2") (pinfunction "2_2") (pintype "passive"))
      (node (ref "U9") (pin "P$3") (pinfunction "VO_P$3") (pintype "bidirectional"))
    )
    (net (code "3") (name "+12V") (class "Default")
      (node (ref "AMPSEAL1") (pin "2") (pinfunction "2_2") (pintype "passive"))
      (node (ref "C32") (pin "1") (pinfunction "1_1") (pintype "passive"))
      (node (ref "C33") (pin "1") (pinfunction "1_1") (pintype "passive"))
      (node (ref "C35") (pin "1") (pinfunction "1_1") (pintype "passive"))
      (node (ref "C36") (pin "1") (pinfunction "1_1") (pintype "passive"))
      (node (ref "C38") (pin "1") (pinfunction "1_1") (pintype "passive"))
      (node (ref "C39") (pin "1") (pinfunction "1_1") (pintype "passive"))
      (node (ref "C41") (pin "1") (pinfunction "1_1") (pintype "passive"))
      (node (ref "C42") (pin "1") (pinfunction "1_1") (pintype "passive"))
      (node (ref "C74") (pin "+") (pinfunction "+_+") (pintype "passive"))
      (node (ref "C75") (pin "1") (pinfunction "1_1") (pintype "passive"))
      (node (ref "C76") (pin "1") (pinfunction "1_1") (pintype "passive"))
      (node (ref "PTC") (pin "P$1") (pinfunction "1_P$1") (pintype "passive"))
      (node (ref "R56") (pin "2") (pinfunction "2_2") (pintype "passive"))
      (node (ref "U3") (pin "8") (pinfunction "VDD2_8") (pintype "power_in"))
      (node (ref "U4") (pin "8") (pinfunction "VDD2_8") (pintype "power_in"))
      (node (ref "U5") (pin "8") (pinfunction "VDD2_8") (pintype "power_in"))
      (node (ref "U6") (pin "8") (pinfunction "VDD2_8") (pintype "power_in"))
      (node (ref "U8") (pin "+VIN1") (pinfunction "+VIN1_+VIN1") (pintype "bidirectional"))
      (node (ref "U8") (pin "+VIN2") (pinfunction "+VIN2_+VIN2") (pintype "bidirectional"))
      (node (ref "U9") (pin "P$1") (pinfunction "VI_P$1") (pintype "bidirectional"))
    )
    (net (code "4") (name "/A0") (class "Default")
      (node (ref "C55") (pin "1") (pinfunction "1_1") (pintype "passive"))
      (node (ref "IC5") (pin "6") (pinfunction "OUT_6") (pintype "output"))
      (node (ref "R26") (pin "2") (pinfunction "2_2") (pintype "passive"))
      (node (ref "U1") (pin "78") (pinfunction "PA16_78") (pintype "bidirectional"))
    )
    (net (code "5") (name "/A1") (class "Default")
      (node (ref "C44") (pin "1") (pinfunction "1_1") (pintype "passive"))
      (node (ref "IC2") (pin "6") (pinfunction "OUT_6") (pintype "output"))
      (node (ref "R15") (pin "2") (pinfunction "2_2") (pintype "passive"))
      (node (ref "U1") (pin "79") (pinfunction "PA24_79") (pintype "bidirectional"))
    )
    (net (code "6") (name "/A2") (class "Default")
      (node (ref "C56") (pin "1") (pinfunction "1_1") (pintype "passive"))
      (node (ref "IC6") (pin "6") (pinfunction "OUT_6") (pintype "output"))
      (node (ref "R27") (pin "2") (pinfunction "2_2") (pintype "passive"))
      (node (ref "U1") (pin "80") (pinfunction "PA23_80") (pintype "bidirectional"))
    )
    (net (code "7") (name "/A3") (class "Default")
      (node (ref "C43") (pin "1") (pinfunction "1_1") (pintype "passive"))
      (node (ref "IC1") (pin "6") (pinfunction "OUT_6") (pintype "output"))
      (node (ref "R14") (pin "2") (pinfunction "2_2") (pintype "passive"))
      (node (ref "U1") (pin "81") (pinfunction "PA22_81") (pintype "bidirectional"))
    )
    (net (code "8") (name "/AIN0") (class "Default")
      (node (ref "AMPSEAL1") (pin "20") (pinfunction "20_20") (pintype "passive"))
      (node (ref "R16") (pin "2") (pinfunction "2_2") (pintype "passive"))
    )
    (net (code "9") (name "/AIN1") (class "Default")
      (node (ref "AMPSEAL1") (pin "21") (pinfunction "21_21") (pintype "passive"))
      (node (ref "R30") (pin "2") (pinfunction "2_2") (pintype "passive"))
    )
    (net (code "10") (name "/AIN2") (class "Default")
      (node (ref "AMPSEAL1") (pin "22") (pinfunction "22_22") (pintype "passive"))
      (node (ref "R18") (pin "2") (pinfunction "2_2") (pintype "passive"))
    )
    (net (code "11") (name "/AIN3") (class "Default")
      (node (ref "AMPSEAL1") (pin "23") (pinfunction "23_23") (pintype "passive"))
      (node (ref "R28") (pin "2") (pinfunction "2_2") (pintype "passive"))
    )
    (net (code "12") (name "/AVREF") (class "Default")
      (node (ref "C20") (pin "1") (pinfunction "1_1") (pintype "passive"))
      (node (ref "L3") (pin "2") (pinfunction "2_2") (pintype "passive"))
      (node (ref "U1") (pin "75") (pinfunction "ADVREF_75") (pintype "power_in"))
    )
    (net (code "13") (name "/CANH0") (class "Default")
      (node (ref "AMPSEAL1") (pin "9") (pinfunction "9_9") (pintype "passive"))
      (node (ref "IC9") (pin "12") (pinfunction "CANH_12") (pintype "input"))
      (node (ref "SJ1") (pin "1") (pinfunction "1_1") (pintype "passive"))
    )
    (net (code "14") (name "/CANH1") (class "Default")
      (node (ref "AMPSEAL1") (pin "11") (pinfunction "11_11") (pintype "passive"))
      (node (ref "IC10") (pin "12") (pinfunction "CANH_12") (pintype "input"))
      (node (ref "SJ3") (pin "1") (pinfunction "1_1") (pintype "passive"))
    )
    (net (code "15") (name "/CANL0") (class "Default")
      (node (ref "AMPSEAL1") (pin "10") (pinfunction "10_10") (pintype "passive"))
      (node (ref "IC9") (pin "13") (pinfunction "CANL_13") (pintype "input"))
      (node (ref "SJ2") (pin "1") (pinfunction "1_1") (pintype "passive"))
    )
    (net (code "16") (name "/CANL1") (class "Default")
      (node (ref "AMPSEAL1") (pin "12") (pinfunction "12_12") (pintype "passive"))
      (node (ref "IC10") (pin "13") (pinfunction "CANL_13") (pintype "input"))
      (node (ref "SJ4") (pin "1") (pinfunction "1_1") (pintype "passive"))
    )
    (net (code "17") (name "/CANRX0") (class "Default")
      (node (ref "IC9") (pin "3") (pinfunction "RXD_3") (pintype "input"))
      (node (ref "U1") (pin "24") (pinfunction "PA1_24") (pintype "bidirectional"))
    )
    (net (code "18") (name "/CANRX1") (class "Default")
      (node (ref "IC10") (pin "3") (pinfunction "RXD_3") (pintype "input"))
      (node (ref "U1") (pin "76") (pinfunction "PB15_76") (pintype "bidirectional"))
    )
    (net (code "19") (name "/CANTX0") (class "Default")
      (node (ref "IC9") (pin "6") (pinfunction "TXD_6") (pintype "input"))
      (node (ref "U1") (pin "23") (pinfunction "PA0_23") (pintype "bidirectional"))
    )
    (net (code "20") (name "/CANTX1") (class "Default")
      (node (ref "IC10") (pin "6") (pinfunction "TXD_6") (pintype "input"))
      (node (ref "U1") (pin "140") (pinfunction "PB14_140") (pintype "bidirectional"))
    )
    (net (code "21") (name "/D+") (class "Default")
      (node (ref "R3") (pin "1") (pinfunction "1_1") (pintype "passive"))
      (node (ref "U1") (pin "37") (pinfunction "DHSDP_37") (pintype "bidirectional"))
      (node (ref "X1") (pin "3") (pinfunction "3_3") (pintype "passive"))
      (node (ref "Z1") (pin "1") (pinfunction "1_1") (pintype "passive"))
    )
    (net (code "22") (name "/D-") (class "Default")
      (node (ref "R2") (pin "1") (pinfunction "1_1") (pintype "passive"))
      (node (ref "U1") (pin "38") (pinfunction "DHSDM_38") (pintype "bidirectional"))
      (node (ref "X1") (pin "2") (pinfunction "2_2") (pintype "passive"))
      (node (ref "Z2") (pin "1") (pinfunction "1_1") (pintype "passive"))
    )
    (net (code "23") (name "/D2") (class "Default")
      (node (ref "U1") (pin "144") (pinfunction "PB25_144") (pintype "bidirectional"))
      (node (ref "U4") (pin "3") (pinfunction "VIB_3") (pintype "input"))
    )
    (net (code "24") (name "/D3") (class "Default")
      (node (ref "U1") (pin "139") (pinfunction "PC28_139") (pintype "bidirectional"))
      (node (ref "U4") (pin "2") (pinfunction "VIA_2") (pintype "input"))
    )
    (net (code "25") (name "/D4") (class "Default")
      (node (ref "U1") (pin "137") (pinfunction "PC26_137") (pintype "bidirectional"))
      (node (ref "U6") (pin "3") (pinfunction "VIB_3") (pintype "input"))
    )
    (net (code "26") (name "/D5") (class "Default")
      (node (ref "U1") (pin "136") (pinfunction "PC25_136") (pintype "bidirectional"))
      (node (ref "U6") (pin "2") (pinfunction "VIA_2") (pintype "input"))
    )
    (net (code "27") (name "/D6") (class "Default")
      (node (ref "U1") (pin "135") (pinfunction "PC24_135") (pintype "bidirectional"))
      (node (ref "U5") (pin "3") (pinfunction "VIB_3") (pintype "input"))
    )
    (net (code "28") (name "/D7") (class "Default")
      (node (ref "U1") (pin "134") (pinfunction "PC23_134") (pintype "bidirectional"))
      (node (ref "U5") (pin "2") (pinfunction "VIA_2") (pintype "input"))
    )
    (net (code "29") (name "/D8") (class "Default")
      (node (ref "U1") (pin "133") (pinfunction "PC22_133") (pintype "bidirectional"))
      (node (ref "U3") (pin "3") (pinfunction "VIB_3") (pintype "input"))
    )
    (net (code "30") (name "/D9") (class "Default")
      (node (ref "U1") (pin "132") (pinfunction "PC21_132") (pintype "bidirectional"))
      (node (ref "U3") (pin "2") (pinfunction "VIA_2") (pintype "input"))
    )
    (net (code "31") (name "/D13") (class "Default")
      (node (ref "R5") (pin "2") (pinfunction "2_2") (pintype "passive"))
      (node (ref "U1") (pin "68") (pinfunction "PB27_68") (pintype "bidirectional"))
    )
    (net (code "32") (name "/D18") (class "Default")
      (node (ref "U$1") (pin "P9") (pinfunction "RESET_P9") (pintype "bidirectional"))
      (node (ref "U1") (pin "4") (pinfunction "PA11_4") (pintype "bidirectional"))
    )
    (net (code "33") (name "/D42") (class "Default")
      (node (ref "U$1") (pin "P8") (pinfunction "MSEL_P8") (pintype "bidirectional"))
      (node (ref "U1") (pin "71") (pinfunction "PA19_71") (pintype "bidirectional"))
    )
    (net (code "34") (name "/D48") (class "Default")
      (node (ref "R42") (pin "1") (pinfunction "1_1") (pintype "passive"))
      (node (ref "R45") (pin "2") (pinfunction "2_2") (pintype "passive"))
      (node (ref "U1") (pin "97") (pinfunction "PC15_97") (pintype "bidirectional"))
    )
    (net (code "35") (name "/D49") (class "Default")
      (node (ref "R43") (pin "1") (pinfunction "1_1") (pintype "passive"))
      (node (ref "R47") (pin "2") (pinfunction "2_2") (pintype "passive"))
      (node (ref "U1") (pin "96") (pinfunction "PC14_96") (pintype "bidirectional"))
    )
    (net (code "36") (name "/D50") (class "Default")
      (node (ref "R48") (pin "1") (pinfunction "1_1") (pintype "passive"))
      (node (ref "R51") (pin "2") (pinfunction "2_2") (pintype "passive"))
      (node (ref "U1") (pin "95") (pinfunction "PC13_95") (pintype "bidirectional"))
    )
    (net (code "37") (name "/D51") (class "Default")
      (node (ref "R49") (pin "1") (pinfunction "1_1") (pintype "passive"))
      (node (ref "R53") (pin "2") (pinfunction "2_2") (pintype "passive"))
      (node (ref "U1") (pin "94") (pinfunction "PC12_94") (pintype "bidirectional"))
    )
    (net (code "38") (name "/DIN0") (class "Default")
      (node (ref "AMPSEAL1") (pin "32") (pinfunction "32_32") (pintype "passive"))
      (node (ref "R44") (pin "1") (pinfunction "1_1") (pintype "passive"))
    )
    (net (code "39") (name "/DIN1") (class "Default")
      (node (ref "AMPSEAL1") (pin "33") (pinfunction "33_33") (pintype "passive"))
      (node (ref "R46") (pin "1") (pinfunction "1_1") (pintype "passive"))
    )
    (net (code "40") (name "/DIN2") (class "Default")
      (node (ref "AMPSEAL1") (pin "34") (pinfunction "34_34") (pintype "passive"))
      (node (ref "R50") (pin "1") (pinfunction "1_1") (pintype "passive"))
    )
    (net (code "41") (name "/DIN3") (class "Default")
      (node (ref "AMPSEAL1") (pin "35") (pinfunction "35_35") (pintype "passive"))
      (node (ref "R52") (pin "1") (pinfunction "1_1") (pintype "passive"))
    )
    (net (code "42") (name "/DOUT0") (class "Default")
      (node (ref "AMPSEAL1") (pin "3") (pinfunction "3_3") (pintype "passive"))
      (node (ref "D1") (pin "C") (pinfunction "C_C") (pintype "passive"))
      (node (ref "T1") (pin "2") (pinfunction "D_2") (pintype "passive"))
      (node (ref "T1") (pin "4") (pinfunction "D_4") (pintype "passive"))
    )
    (net (code "43") (name "/DOUT1") (class "Default")
      (node (ref "AMPSEAL1") (pin "4") (pinfunction "4_4") (pintype "passive"))
      (node (ref "D2") (pin "C") (pinfunction "C_C") (pintype "passive"))
      (node (ref "T2") (pin "2") (pinfunction "D_2") (pintype "passive"))
      (node (ref "T2") (pin "4") (pinfunction "D_4") (pintype "passive"))
    )
    (net (code "44") (name "/DOUT2") (class "Default")
      (node (ref "AMPSEAL1") (pin "5") (pinfunction "5_5") (pintype "passive"))
      (node (ref "D3") (pin "C") (pinfunction "C_C") (pintype "passive"))
      (node (ref "T3") (pin "2") (pinfunction "D_2") (pintype "passive"))
      (node (ref "T3") (pin "4") (pinfunction "D_4") (pintype "passive"))
    )
    (net (code "45") (name "/DOUT3") (class "Default")
      (node (ref "AMPSEAL1") (pin "6") (pinfunction "6_6") (pintype "passive"))
      (node (ref "D4") (pin "C") (pinfunction "C_C") (pintype "passive"))
      (node (ref "T4") (pin "2") (pinfunction "D_2") (pintype "passive"))
      (node (ref "T4") (pin "4") (pinfunction "D_4") (pintype "passive"))
    )
    (net (code "46") (name "/DOUT4") (class "Default")
      (node (ref "AMPSEAL1") (pin "15") (pinfunction "15_15") (pintype "passive"))
      (node (ref "D5") (pin "C") (pinfunction "C_C") (pintype "passive"))
      (node (ref "T5") (pin "2") (pinfunction "D_2") (pintype "passive"))
      (node (ref "T5") (pin "4") (pinfunction "D_4") (pintype "passive"))
    )
    (net (code "47") (name "/DOUT5") (class "Default")
      (node (ref "AMPSEAL1") (pin "16") (pinfunction "16_16") (pintype "passive"))
      (node (ref "D6") (pin "C") (pinfunction "C_C") (pintype "passive"))
      (node (ref "T6") (pin "2") (pinfunction "D_2") (pintype "passive"))
      (node (ref "T6") (pin "4") (pinfunction "D_4") (pintype "passive"))
    )
    (net (code "48") (name "/DOUT6") (class "Default")
      (node (ref "AMPSEAL1") (pin "17") (pinfunction "17_17") (pintype "passive"))
      (node (ref "D7") (pin "C") (pinfunction "C_C") (pintype "passive"))
      (node (ref "T7") (pin "2") (pinfunction "D_2") (pintype "passive"))
      (node (ref "T7") (pin "4") (pinfunction "D_4") (pintype "passive"))
    )
    (net (code "49") (name "/DOUT7") (class "Default")
      (node (ref "AMPSEAL1") (pin "18") (pinfunction "18_18") (pintype "passive"))
      (node (ref "D8") (pin "C") (pinfunction "C_C") (pintype "passive"))
      (node (ref "T8") (pin "2") (pinfunction "D_2") (pintype "passive"))
      (node (ref "T8") (pin "4") (pinfunction "D_4") (pintype "passive"))
    )
    (net (code "50") (name "/GPIO0") (class "Default")
      (node (ref "U1") (pin "93") (pinfunction "PC11_93") (pintype "bidirectional"))
    )
    (net (code "51") (name "/GPIO1") (class "Default")
      (node (ref "U1") (pin "92") (pinfunction "PB21_92") (pintype "bidirectional"))
    )
    (net (code "52") (name "/GPIO2") (class "Default")
      (node (ref "JP1") (pin "5") (pinfunction "5_5") (pintype "passive"))
      (node (ref "U1") (pin "91") (pinfunction "PB20_91") (pintype "bidirectional"))
    )
    (net (code "53") (name "/GPIO3") (class "Default")
      (node (ref "JP1") (pin "3") (pinfunction "3_3") (pintype "passive"))
      (node (ref "U1") (pin "90") (pinfunction "PB19_90") (pintype "bidirectional"))
    )
    (net (code "54") (name "/GPIO4") (class "Default")
      (node (ref "JP1") (pin "1") (pinfunction "1_1") (pintype "passive"))
      (node (ref "U1") (pin "88") (pinfunction "PB17_88") (pintype "bidirectional"))
    )
    (net (code "55") (name "/MASTER-RESET") (class "Default")
      (node (ref "C28") (pin "2") (pinfunction "2_2") (pintype "passive"))
      (node (ref "RESET") (pin "P$2") (pinfunction "P$5_P$2") (pintype "bidirectional"))
      (node (ref "U1") (pin "47") (pinfunction "NRSTB_47") (pintype "input"))
    )
    (net (code "56") (name "/MDRIVE0") (class "Default")
      (node (ref "R12") (pin "1") (pinfunction "1_1") (pintype "passive"))
      (node (ref "T1") (pin "1") (pinfunction "G_1") (pintype "passive"))
      (node (ref "U6") (pin "6") (pinfunction "VOB_6") (pintype "output"))
    )
    (net (code "57") (name "/MDRIVE1") (class "Default")
      (node (ref "R13") (pin "1") (pinfunction "1_1") (pintype "passive"))
      (node (ref "T2") (pin "1") (pinfunction "G_1") (pintype "passive"))
      (node (ref "U6") (pin "7") (pinfunction "VOA_7") (pintype "output"))
    )
    (net (code "58") (name "/MDRIVE2") (class "Default")
      (node (ref "R10") (pin "1") (pinfunction "1_1") (pintype "passive"))
      (node (ref "T3") (pin "1") (pinfunction "G_1") (pintype "passive"))
      (node (ref "U5") (pin "6") (pinfunction "VOB_6") (pintype "output"))
    )
    (net (code "59") (name "/MDRIVE3") (class "Default")
      (node (ref "R11") (pin "1") (pinfunction "1_1") (pintype "passive"))
      (node (ref "T4") (pin "1") (pinfunction "G_1") (pintype "passive"))
      (node (ref "U5") (pin "7") (pinfunction "VOA_7") (pintype "output"))
    )
    (net (code "60") (name "/MDRIVE4") (class "Default")
      (node (ref "R8") (pin "1") (pinfunction "1_1") (pintype "passive"))
      (node (ref "T5") (pin "1") (pinfunction "G_1") (pintype "passive"))
      (node (ref "U4") (pin "6") (pinfunction "VOB_6") (pintype "output"))
    )
    (net (code "61") (name "/MDRIVE5") (class "Default")
      (node (ref "R9") (pin "1") (pinfunction "1_1") (pintype "passive"))
      (node (ref "T6") (pin "1") (pinfunction "G_1") (pintype "passive"))
      (node (ref "U4") (pin "7") (pinfunction "VOA_7") (pintype "output"))
    )
    (net (code "62") (name "/MDRIVE6") (class "Default")
      (node (ref "R6") (pin "1") (pinfunction "1_1") (pintype "passive"))
      (node (ref "T7") (pin "1") (pinfunction "G_1") (pintype "passive"))
      (node (ref "U3") (pin "6") (pinfunction "VOB_6") (pintype "output"))
    )
    (net (code "63") (name "/MDRIVE7") (class "Default")
      (node (ref "R7") (pin "1") (pinfunction "1_1") (pintype "passive"))
      (node (ref "T8") (pin "1") (pinfunction "G_1") (pintype "passive"))
      (node (ref "U3") (pin "7") (pinfunction "VOA_7") (pintype "output"))
    )
    (net (code "64") (name "/RX2") (class "Default")
      (node (ref "U$1") (pin "P4") (pinfunction "TXD0_P4") (pintype "bidirectional"))
      (node (ref "U1") (pin "5") (pinfunction "PA12_5") (pintype "bidirectional"))
    )
    (net (code "65") (name "/RX3") (class "Default")
      (node (ref "JP1") (pin "4") (pinfunction "4_4") (pintype "passive"))
      (node (ref "JP1") (pin "7") (pinfunction "7_7") (pintype "passive"))
      (node (ref "U1") (pin "18") (pinfunction "PD5_18") (pintype "bidirectional"))
    )
    (net (code "66") (name "/SCL") (class "Default")
      (node (ref "R54") (pin "2") (pinfunction "2_2") (pintype "passive"))
      (node (ref "U1") (pin "87") (pinfunction "PB13_87") (pintype "bidirectional"))
      (node (ref "U7") (pin "PIN6") (pinfunction "SCL_PIN6") (pintype "bidirectional"))
    )
    (net (code "67") (name "/SDA") (class "Default")
      (node (ref "R55") (pin "2") (pinfunction "2_2") (pintype "passive"))
      (node (ref "U1") (pin "86") (pinfunction "PB12_86") (pintype "bidirectional"))
      (node (ref "U7") (pin "PIN5") (pinfunction "SDA_PIN5") (pintype "bidirectional"))
    )
    (net (code "68") (name "/TX2") (class "Default")
      (node (ref "U$1") (pin "P3") (pinfunction "RXD0_P3") (pintype "bidirectional"))
      (node (ref "U1") (pin "6") (pinfunction "PA13_6") (pintype "bidirectional"))
    )
    (net (code "69") (name "/TX3") (class "Default")
      (node (ref "JP1") (pin "2") (pinfunction "2_2") (pintype "passive"))
      (node (ref "U1") (pin "17") (pinfunction "PD4_17") (pintype "bidirectional"))
    )
    (net (code "70") (name "/VBG") (class "Default")
      (node (ref "C27") (pin "1") (pinfunction "1_1") (pintype "passive"))
      (node (ref "R4") (pin "2") (pinfunction "2_2") (pintype "passive"))
      (node (ref "U1") (pin "40") (pinfunction "VBG_40") (pintype "passive"))
    )
    (net (code "71") (name "/VBUS") (class "Default")
      (node (ref "C29") (pin "1") (pinfunction "1_1") (pintype "passive"))
      (node (ref "U1") (pin "39") (pinfunction "VBUS_39") (pintype "power_in"))
      (node (ref "U2") (pin "3") (pinfunction "IN_3") (pintype "input"))
      (node (ref "X1") (pin "1") (pinfunction "1_1") (pintype "passive"))
    )
    (net (code "72") (name "/VDDANA") (class "Default")
      (node (ref "C10") (pin "1") (pinfunction "1_1") (pintype "passive"))
      (node (ref "C11") (pin "1") (pinfunction "1_1") (pintype "passive"))
      (node (ref "L1") (pin "2") (pinfunction "2_2") (pintype "passive"))
      (node (ref "U1") (pin "73") (pinfunction "VDDANA_73") (pintype "power_in"))
    )
    (net (code "73") (name "/VDDOUT") (class "Default")
      (node (ref "C12") (pin "1") (pinfunction "1_1") (pintype "passive"))
      (node (ref "C13") (pin "1") (pinfunction "1_1") (pintype "passive"))
      (node (ref "C14") (pin "1") (pinfunction "1_1") (pintype "passive"))
      (node (ref "C15") (pin "1") (pinfunction "1_1") (pintype "passive"))
      (node (ref "C16") (pin "1") (pinfunction "1_1") (pintype "passive"))
      (node (ref "C17") (pin "1") (pinfunction "1_1") (pintype "passive"))
      (node (ref "C18") (pin "1") (pinfunction "1_1") (pintype "passive"))
      (node (ref "L4") (pin "1") (pinfunction "1_1") (pintype "passive"))
      (node (ref "U1") (pin "10") (pinfunction "VDDCORE1_10") (pintype "input"))
      (node (ref "U1") (pin "104") (pinfunction "VDDCORE4_104") (pintype "input"))
      (node (ref "U1") (pin "124") (pinfunction "VDDCORE5_124") (pintype "input"))
      (node (ref "U1") (pin "45") (pinfunction "VDDCORE2_45") (pintype "input"))
      (node (ref "U1") (pin "56") (pinfunction "VDDOUT_56") (pintype "output"))
      (node (ref "U1") (pin "61") (pinfunction "VDDCORE3_61") (pintype "input"))
    )
    (net (code "74") (name "/VDDOUTMI") (class "Default")
      (node (ref "C8") (pin "1") (pinfunction "1_1") (pintype "passive"))
      (node (ref "C9") (pin "1") (pinfunction "1_1") (pintype "passive"))
      (node (ref "L2") (pin "2") (pinfunction "2_2") (pintype "passive"))
      (node (ref "U1") (pin "41") (pinfunction "VDDUTMI_41") (pintype "input"))
    )
    (net (code "75") (name "/VDDPLL") (class "Default")
      (node (ref "C21") (pin "1") (pinfunction "1_1") (pintype "passive"))
      (node (ref "C22") (pin "1") (pinfunction "1_1") (pintype "passive"))
      (node (ref "L4") (pin "2") (pinfunction "2_2") (pintype "passive"))
      (node (ref "U1") (pin "34") (pinfunction "VDDPLL_34") (pintype "input"))
    )
    (net (code "76") (name "/VIN(+12V)") (class "Default")
      (node (ref "AMPSEAL1") (pin "1") (pinfunction "1_1") (pintype "passive"))
      (node (ref "D9") (pin "A") (pinfunction "A_A") (pintype "passive"))
    )
    (net (code "77") (name "/XIN") (class "Default")
      (node (ref "C24") (pin "1") (pinfunction "1_1") (pintype "passive"))
      (node (ref "U1") (pin "36") (pinfunction "XIN_36") (pintype "input"))
      (node (ref "Y1") (pin "1") (pinfunction "C1_1") (pintype "passive"))
    )
    (net (code "78") (name "/XIN32") (class "Default")
      (node (ref "C26") (pin "1") (pinfunction "1_1") (pintype "passive"))
      (node (ref "U1") (pin "48") (pinfunction "XIN32_48") (pintype "output"))
      (node (ref "Y2") (pin "P$2") (pinfunction "2_P$2") (pintype "bidirectional"))
    )
    (net (code "79") (name "/XOUT") (class "Default")
      (node (ref "C23") (pin "1") (pinfunction "1_1") (pintype "passive"))
      (node (ref "U1") (pin "35") (pinfunction "XOUT_35") (pintype "output"))
      (node (ref "Y1") (pin "3") (pinfunction "C2_3") (pintype "passive"))
    )
    (net (code "80") (name "/XOUT32") (class "Default")
      (node (ref "C25") (pin "1") (pinfunction "1_1") (pintype "passive"))
      (node (ref "U1") (pin "49") (pinfunction "XOUT32_49") (pintype "output"))
      (node (ref "Y2") (pin "P$1") (pinfunction "1_P$1") (pintype "bidirectional"))
    )
    (net (code "81") (name "GND") (class "Default")
      (node (ref "+12V") (pin "C") (pinfunction "C_C") (pintype "passive"))
      (node (ref "+5V") (pin "C") (pinfunction "C_C") (pintype "passive"))
      (node (ref "AMPSEAL1") (pin "13") (pinfunction "13_13") (pintype "passive"))
      (node (ref "AMPSEAL1") (pin "14") (pinfunction "14_14") (pintype "passive"))
      (node (ref "AMPSEAL1") (pin "19") (pinfunction "19_19") (pintype "passive"))
      (node (ref "AMPSEAL1") (pin "29") (pinfunction "29_29") (pintype "passive"))
      (node (ref "AMPSEAL1") (pin "30") (pinfunction "30_30") (pintype "passive"))
      (node (ref "AMPSEAL1") (pin "31") (pinfunction "31_31") (pintype "passive"))
      (node (ref "AMPSEAL1") (pin "7") (pinfunction "7_7") (pintype "passive"))
      (node (ref "AMPSEAL1") (pin "8") (pinfunction "8_8") (pintype "passive"))
      (node (ref "C32") (pin "2") (pinfunction "2_2") (pintype "passive"))
      (node (ref "C33") (pin "2") (pinfunction "2_2") (pintype "passive"))
      (node (ref "C35") (pin "2") (pinfunction "2_2") (pintype "passive"))
      (node (ref "C36") (pin "2") (pinfunction "2_2") (pintype "passive"))
      (node (ref "C38") (pin "2") (pinfunction "2_2") (pintype "passive"))
      (node (ref "C39") (pin "2") (pinfunction "2_2") (pintype "passive"))
      (node (ref "C41") (pin "2") (pinfunction "2_2") (pintype "passive"))
      (node (ref "C42") (pin "2") (pinfunction "2_2") (pintype "passive"))
      (node (ref "C47") (pin "2") (pinfunction "2_2") (pintype "passive"))
      (node (ref "C48") (pin "2") (pinfunction "2_2") (pintype "passive"))
      (node (ref "C49") (pin "2") (pinfunction "2_2") (pintype "passive"))
      (node (ref "C50") (pin "2") (pinfunction "2_2") (pintype "passive"))
      (node (ref "C58") (pin "2") (pinfunction "2_2") (pintype "passive"))
      (node (ref "C59") (pin "2") (pinfunction "2_2") (pintype "passive"))
      (node (ref "C63") (pin "2") (pinfunction "2_2") (pintype "passive"))
      (node (ref "C64") (pin "2") (pinfunction "2_2") (pintype "passive"))
      (node (ref "C68") (pin "2") (pinfunction "2_2") (pintype "passive"))
      (node (ref "C69") (pin "2") (pinfunction "2_2") (pintype "passive"))
      (node (ref "C71") (pin "2") (pinfunction "2_2") (pintype "passive"))
      (node (ref "C72") (pin "2") (pinfunction "2_2") (pintype "passive"))
      (node (ref "C74") (pin "-") (pinfunction "-_-") (pintype "passive"))
      (node (ref "C75") (pin "2") (pinfunction "2_2") (pintype "passive"))
      (node (ref "C76") (pin "2") (pinfunction "2_2") (pintype "passive"))
      (node (ref "C78") (pin "1") (pinfunction "1_1") (pintype "passive"))
      (node (ref "D1") (pin "A") (pinfunction "A_A") (pintype "passive"))
      (node (ref "D2") (pin "A") (pinfunction "A_A") (pintype "passive"))
      (node (ref "D3") (pin "A") (pinfunction "A_A") (pintype "passive"))
      (node (ref "D4") (pin "A") (pinfunction "A_A") (pintype "passive"))
      (node (ref "D5") (pin "A") (pinfunction "A_A") (pintype "passive"))
      (node (ref "D6") (pin "A") (pinfunction "A_A") (pintype "passive"))
      (node (ref "D7") (pin "A") (pinfunction "A_A") (pintype "passive"))
      (node (ref "D8") (pin "A") (pinfunction "A_A") (pintype "passive"))
      (node (ref "IC10") (pin "10") (pinfunction "GND2_10") (pintype "input"))
      (node (ref "IC10") (pin "15") (pinfunction "GND2_15") (pintype "input"))
      (node (ref "IC10") (pin "16") (pinfunction "GND2_16") (pintype "input"))
      (node (ref "IC3") (pin "3") (pinfunction "SHDN_3") (pintype "bidirectional"))
      (node (ref "IC3") (pin "4") (pinfunction "GND1_4") (pintype "bidirectional"))
      (node (ref "IC4") (pin "3") (pinfunction "SHDN_3") (pintype "bidirectional"))
      (node (ref "IC4") (pin "4") (pinfunction "GND1_4") (pintype "bidirectional"))
      (node (ref "IC7") (pin "3") (pinfunction "SHDN_3") (pintype "bidirectional"))
      (node (ref "IC7") (pin "4") (pinfunction "GND1_4") (pintype "bidirectional"))
      (node (ref "IC8") (pin "3") (pinfunction "SHDN_3") (pintype "bidirectional"))
      (node (ref "IC8") (pin "4") (pinfunction "GND1_4") (pintype "bidirectional"))
      (node (ref "IC9") (pin "10") (pinfunction "GND2_10") (pintype "input"))
      (node (ref "IC9") (pin "15") (pinfunction "GND2_15") (pintype "input"))
      (node (ref "IC9") (pin "16") (pinfunction "GND2_16") (pintype "input"))
      (node (ref "OK1") (pin "2") (pinfunction "C_2") (pintype "passive"))
      (node (ref "OK1") (pin "4") (pinfunction "C_4") (pintype "passive"))
      (node (ref "OK2") (pin "2") (pinfunction "C_2") (pintype "passive"))
      (node (ref "OK2") (pin "4") (pinfunction "C_4") (pintype "passive"))
      (node (ref "R10") (pin "2") (pinfunction "2_2") (pintype "passive"))
      (node (ref "R11") (pin "2") (pinfunction "2_2") (pintype "passive"))
      (node (ref "R12") (pin "2") (pinfunction "2_2") (pintype "passive"))
      (node (ref "R13") (pin "2") (pinfunction "2_2") (pintype "passive"))
      (node (ref "R20") (pin "1") (pinfunction "1_1") (pintype "passive"))
      (node (ref "R22") (pin "1") (pinfunction "1_1") (pintype "passive"))
      (node (ref "R32") (pin "1") (pinfunction "1_1") (pintype "passive"))
      (node (ref "R34") (pin "1") (pinfunction "1_1") (pintype "passive"))
      (node (ref "R6") (pin "2") (pinfunction "2_2") (pintype "passive"))
      (node (ref "R7") (pin "2") (pinfunction "2_2") (pintype "passive"))
      (node (ref "R8") (pin "2") (pinfunction "2_2") (pintype "passive"))
      (node (ref "R9") (pin "2") (pinfunction "2_2") (pintype "passive"))
      (node (ref "T1") (pin "3") (pinfunction "S_3") (pintype "passive"))
      (node (ref "T2") (pin "3") (pinfunction "S_3") (pintype "passive"))
      (node (ref "T3") (pin "3") (pinfunction "S_3") (pintype "passive"))
      (node (ref "T4") (pin "3") (pinfunction "S_3") (pintype "passive"))
      (node (ref "T5") (pin "3") (pinfunction "S_3") (pintype "passive"))
      (node (ref "T6") (pin "3") (pinfunction "S_3") (pintype "passive"))
      (node (ref "T7") (pin "3") (pinfunction "S_3") (pintype "passive"))
      (node (ref "T8") (pin "3") (pinfunction "S_3") (pintype "passive"))
      (node (ref "TVS") (pin "A") (pinfunction "A_A") (pintype "passive"))
      (node (ref "U3") (pin "5") (pinfunction "GND2_5") (pintype "passive"))
      (node (ref "U4") (pin "5") (pinfunction "GND2_5") (pintype "passive"))
      (node (ref "U5") (pin "5") (pinfunction "GND2_5") (pintype "passive"))
      (node (ref "U6") (pin "5") (pinfunction "GND2_5") (pintype "passive"))
      (node (ref "U8") (pin "-VIN1") (pinfunction "-VIN1_-VIN1") (pintype "bidirectional"))
      (node (ref "U8") (pin "-VIN2") (pinfunction "-VIN2_-VIN2") (pintype "bidirectional"))
      (node (ref "U9") (pin "P$2") (pinfunction "GND_P$2") (pintype "bidirectional"))
      (node (ref "ZEN") (pin "A") (pinfunction "A_A") (pintype "passive"))
    )
    (net (code "82") (name "IGND") (class "Default")
      (node (ref "+3.3V") (pin "C") (pinfunction "C_C") (pintype "passive"))
      (node (ref "C1") (pin "2") (pinfunction "2_2") (pintype "passive"))
      (node (ref "C10") (pin "2") (pinfunction "2_2") (pintype "passive"))
      (node (ref "C11") (pin "2") (pinfunction "2_2") (pintype "passive"))
      (node (ref "C12") (pin "2") (pinfunction "2_2") (pintype "passive"))
      (node (ref "C13") (pin "2") (pinfunction "2_2") (pintype "passive"))
      (node (ref "C14") (pin "2") (pinfunction "2_2") (pintype "passive"))
      (node (ref "C15") (pin "2") (pinfunction "2_2") (pintype "passive"))
      (node (ref "C16") (pin "2") (pinfunction "2_2") (pintype "passive"))
      (node (ref "C17") (pin "2") (pinfunction "2_2") (pintype "passive"))
      (node (ref "C18") (pin "2") (pinfunction "2_2") (pintype "passive"))
      (node (ref "C19") (pin "2") (pinfunction "2_2") (pintype "passive"))
      (node (ref "C2") (pin "2") (pinfunction "2_2") (pintype "passive"))
      (node (ref "C20") (pin "2") (pinfunction "2_2") (pintype "passive"))
      (node (ref "C21") (pin "2") (pinfunction "2_2") (pintype "passive"))
      (node (ref "C22") (pin "2") (pinfunction "2_2") (pintype "passive"))
      (node (ref "C23") (pin "2") (pinfunction "2_2") (pintype "passive"))
      (node (ref "C24") (pin "2") (pinfunction "2_2") (pintype "passive"))
      (node (ref "C25") (pin "2") (pinfunction "2_2") (pintype "passive"))
      (node (ref "C26") (pin "2") (pinfunction "2_2") (pintype "passive"))
      (node (ref "C27") (pin "2") (pinfunction "2_2") (pintype "passive"))
      (node (ref "C29") (pin "2") (pinfunction "2_2") (pintype "passive"))
      (node (ref "C3") (pin "2") (pinfunction "2_2") (pintype "passive"))
      (node (ref "C30") (pin "2") (pinfunction "2_2") (pintype "passive"))
      (node (ref "C31") (pin "2") (pinfunction "2_2") (pintype "passive"))
      (node (ref "C34") (pin "2") (pinfunction "2_2") (pintype "passive"))
      (node (ref "C37") (pin "2") (pinfunction "2_2") (pintype "passive"))
      (node (ref "C4") (pin "2") (pinfunction "2_2") (pintype "passive"))
      (node (ref "C40") (pin "2") (pinfunction "2_2") (pintype "passive"))
      (node (ref "C45") (pin "2") (pinfunction "2_2") (pintype "passive"))
      (node (ref "C46") (pin "2") (pinfunction "2_2") (pintype "passive"))
      (node (ref "C5") (pin "2") (pinfunction "2_2") (pintype "passive"))
      (node (ref "C51") (pin "2") (pinfunction "2_2") (pintype "passive"))
      (node (ref "C52") (pin "2") (pinfunction "2_2") (pintype "passive"))
      (node (ref "C53") (pin "2") (pinfunction "2_2") (pintype "passive"))
      (node (ref "C54") (pin "2") (pinfunction "2_2") (pintype "passive"))
      (node (ref "C57") (pin "2") (pinfunction "2_2") (pintype "passive"))
      (node (ref "C6") (pin "2") (pinfunction "2_2") (pintype "passive"))
      (node (ref "C60") (pin "2") (pinfunction "2_2") (pintype "passive"))
      (node (ref "C61") (pin "2") (pinfunction "2_2") (pintype "passive"))
      (node (ref "C62") (pin "2") (pinfunction "2_2") (pintype "passive"))
      (node (ref "C65") (pin "2") (pinfunction "2_2") (pintype "passive"))
      (node (ref "C66") (pin "2") (pinfunction "2_2") (pintype "passive"))
      (node (ref "C67") (pin "2") (pinfunction "2_2") (pintype "passive"))
      (node (ref "C7") (pin "2") (pinfunction "2_2") (pintype "passive"))
      (node (ref "C70") (pin "2") (pinfunction "2_2") (pintype "passive"))
      (node (ref "C73") (pin "2") (pinfunction "2_2") (pintype "passive"))
      (node (ref "C77") (pin "2") (pinfunction "2_2") (pintype "passive"))
      (node (ref "C78") (pin "2") (pinfunction "2_2") (pintype "passive"))
      (node (ref "C79") (pin "2") (pinfunction "2_2") (pintype "passive"))
      (node (ref "C8") (pin "2") (pinfunction "2_2") (pintype "passive"))
      (node (ref "C9") (pin "2") (pinfunction "2_2") (pintype "passive"))
      (node (ref "IC1") (pin "4") (pinfunction "V-_4") (pintype "power_in"))
      (node (ref "IC10") (pin "2") (pinfunction "GND1_2") (pintype "input"))
      (node (ref "IC10") (pin "7") (pinfunction "GND1_7") (pintype "input"))
      (node (ref "IC10") (pin "8") (pinfunction "GND1_8") (pintype "input"))
      (node (ref "IC2") (pin "4") (pinfunction "V-_4") (pintype "power_in"))
      (node (ref "IC3") (pin "5") (pinfunction "GND2_5") (pintype "bidirectional"))
      (node (ref "IC4") (pin "5") (pinfunction "GND2_5") (pintype "bidirectional"))
      (node (ref "IC5") (pin "4") (pinfunction "V-_4") (pintype "power_in"))
      (node (ref "IC6") (pin "4") (pinfunction "V-_4") (pintype "power_in"))
      (node (ref "IC7") (pin "5") (pinfunction "GND2_5") (pintype "bidirectional"))
      (node (ref "IC8") (pin "5") (pinfunction "GND2_5") (pintype "bidirectional"))
      (node (ref "IC9") (pin "2") (pinfunction "GND1_2") (pintype "input"))
      (node (ref "IC9") (pin "7") (pinfunction "GND1_7") (pintype "input"))
      (node (ref "IC9") (pin "8") (pinfunction "GND1_8") (pintype "input"))
      (node (ref "JP1") (pin "8") (pinfunction "8_8") (pintype "passive"))
      (node (ref "LED") (pin "C") (pinfunction "C_C") (pintype "passive"))
      (node (ref "OK1") (pin "5") (pinfunction "EMIT_5") (pintype "passive"))
      (node (ref "OK1") (pin "7") (pinfunction "EMIT_7") (pintype "passive"))
      (node (ref "OK2") (pin "5") (pinfunction "EMIT_5") (pintype "passive"))
      (node (ref "OK2") (pin "7") (pinfunction "EMIT_7") (pintype "passive"))
      (node (ref "R24") (pin "2") (pinfunction "2_2") (pintype "passive"))
      (node (ref "R25") (pin "2") (pinfunction "2_2") (pintype "passive"))
      (node (ref "R36") (pin "2") (pinfunction "2_2") (pintype "passive"))
      (node (ref "R37") (pin "2") (pinfunction "2_2") (pintype "passive"))
      (node (ref "R4") (pin "1") (pinfunction "1_1") (pintype "passive"))
      (node (ref "RESET") (pin "P$1") (pinfunction "P$4_P$1") (pintype "bidirectional"))
      (node (ref "U$1") (pin "P2") (pinfunction "GND_P2") (pintype "bidirectional"))
      (node (ref "U1") (pin "106") (pinfunction "GND3_106") (pintype "power_in"))
      (node (ref "U1") (pin "12") (pinfunction "GND1_12") (pintype "power_in"))
      (node (ref "U1") (pin "126") (pinfunction "GND4_126") (pintype "power_in"))
      (node (ref "U1") (pin "33") (pinfunction "GNDPLL_33") (pintype "power_in"))
      (node (ref "U1") (pin "44") (pinfunction "GNDUTMI_44") (pintype "power_in"))
      (node (ref "U1") (pin "46") (pinfunction "JTAGSEL_46") (pintype "input"))
      (node (ref "U1") (pin "54") (pinfunction "GNDBU_54") (pintype "power_in"))
      (node (ref "U1") (pin "58") (pinfunction "GND2_58") (pintype "power_in"))
      (node (ref "U1") (pin "74") (pinfunction "GNDANA_74") (pintype "power_in"))
      (node (ref "U2") (pin "1") (pinfunction "ADJ_1") (pintype "input"))
      (node (ref "U3") (pin "4") (pinfunction "GND1_4") (pintype "passive"))
      (node (ref "U4") (pin "4") (pinfunction "GND1_4") (pintype "passive"))
      (node (ref "U5") (pin "4") (pinfunction "GND1_4") (pintype "passive"))
      (node (ref "U6") (pin "4") (pinfunction "GND1_4") (pintype "passive"))
      (node (ref "U7") (pin "PIN1") (pinfunction "NA1_PIN1") (pintype "bidirectional"))
      (node (ref "U7") (pin "PIN2") (pinfunction "NA2_PIN2") (pintype "bidirectional"))
      (node (ref "U7") (pin "PIN3") (pinfunction "E2_PIN3") (pintype "bidirectional"))
      (node (ref "U7") (pin "PIN4") (pinfunction "VSS_PIN4") (pintype "bidirectional"))
      (node (ref "U8") (pin "-VOUT") (pinfunction "-VOUT_-VOUT") (pintype "bidirectional"))
      (node (ref "X1") (pin "4") (pinfunction "4_4") (pintype "passive"))
      (node (ref "Y1") (pin "2") (pinfunction "GND_2") (pintype "passive"))
      (node (ref "Y1") (pin "4") (pinfunction "GND_4") (pintype "passive"))
      (node (ref "Z1") (pin "2") (pinfunction "2_2") (pintype "passive"))
      (node (ref "Z2") (pin "2") (pinfunction "2_2") (pintype "passive"))
    )
    (net (code "83") (name "Net-(+3.3V-PadA)") (class "Default")
      (node (ref "+3.3V") (pin "A") (pinfunction "A_A") (pintype "passive"))
      (node (ref "R58") (pin "1") (pinfunction "1_1") (pintype "passive"))
    )
    (net (code "84") (name "Net-(+5V-PadA)") (class "Default")
      (node (ref "+5V") (pin "A") (pinfunction "A_A") (pintype "passive"))
      (node (ref "R57") (pin "1") (pinfunction "1_1") (pintype "passive"))
    )
    (net (code "85") (name "Net-(+12V-PadA)") (class "Default")
      (node (ref "+12V") (pin "A") (pinfunction "A_A") (pintype "passive"))
      (node (ref "R56") (pin "1") (pinfunction "1_1") (pintype "passive"))
    )
    (net (code "86") (name "Net-(C69-Pad1)") (class "Default")
      (node (ref "C69") (pin "1") (pinfunction "1_1") (pintype "passive"))
      (node (ref "R38") (pin "1") (pinfunction "1_1") (pintype "passive"))
      (node (ref "R39") (pin "1") (pinfunction "1_1") (pintype "passive"))
    )
    (net (code "87") (name "Net-(C72-Pad1)") (class "Default")
      (node (ref "C72") (pin "1") (pinfunction "1_1") (pintype "passive"))
      (node (ref "R40") (pin "1") (pinfunction "1_1") (pintype "passive"))
      (node (ref "R41") (pin "1") (pinfunction "1_1") (pintype "passive"))
    )
    (net (code "88") (name "Net-(ERASE-P$4)") (class "Default")
      (node (ref "ERASE") (pin "P$1") (pinfunction "P$4_P$1") (pintype "bidirectional"))
      (node (ref "U1") (pin "130") (pinfunction "PC0_130") (pintype "bidirectional"))
    )
    (net (code "89") (name "Net-(IC1-+IN)") (class "Default")
      (node (ref "C53") (pin "1") (pinfunction "1_1") (pintype "passive"))
      (node (ref "IC1") (pin "3") (pinfunction "+IN_3") (pintype "input"))
      (node (ref "R21") (pin "2") (pinfunction "2_2") (pintype "passive"))
      (node (ref "R24") (pin "1") (pinfunction "1_1") (pintype "passive"))
    )
    (net (code "90") (name "Net-(IC1--IN)") (class "Default")
      (node (ref "C43") (pin "2") (pinfunction "2_2") (pintype "passive"))
      (node (ref "IC1") (pin "2") (pinfunction "-IN_2") (pintype "input"))
      (node (ref "R14") (pin "1") (pinfunction "1_1") (pintype "passive"))
      (node (ref "R17") (pin "2") (pinfunction "2_2") (pintype "passive"))
    )
    (net (code "91") (name "Net-(IC2-+IN)") (class "Default")
      (node (ref "C54") (pin "1") (pinfunction "1_1") (pintype "passive"))
      (node (ref "IC2") (pin "3") (pinfunction "+IN_3") (pintype "input"))
      (node (ref "R23") (pin "2") (pinfunction "2_2") (pintype "passive"))
      (node (ref "R25") (pin "1") (pinfunction "1_1") (pintype "passive"))
    )
    (net (code "92") (name "Net-(IC2--IN)") (class "Default")
      (node (ref "C44") (pin "2") (pinfunction "2_2") (pintype "passive"))
      (node (ref "IC2") (pin "2") (pinfunction "-IN_2") (pintype "input"))
      (node (ref "R15") (pin "1") (pinfunction "1_1") (pintype "passive"))
      (node (ref "R19") (pin "2") (pinfunction "2_2") (pintype "passive"))
    )
    (net (code "93") (name "Net-(IC3-VIN)") (class "Default")
      (node (ref "C47") (pin "1") (pinfunction "1_1") (pintype "passive"))
      (node (ref "IC3") (pin "2") (pinfunction "VIN_2") (pintype "bidirectional"))
      (node (ref "R16") (pin "1") (pinfunction "1_1") (pintype "passive"))
      (node (ref "R20") (pin "2") (pinfunction "2_2") (pintype "passive"))
    )
    (net (code "94") (name "Net-(IC3-VOUT+)") (class "Default")
      (node (ref "IC3") (pin "7") (pinfunction "VOUT+_7") (pintype "bidirectional"))
      (node (ref "R21") (pin "1") (pinfunction "1_1") (pintype "passive"))
    )
    (net (code "95") (name "Net-(IC3-VOUT-)") (class "Default")
      (node (ref "IC3") (pin "6") (pinfunction "VOUT-_6") (pintype "bidirectional"))
      (node (ref "R17") (pin "1") (pinfunction "1_1") (pintype "passive"))
    )
    (net (code "96") (name "Net-(IC4-VIN)") (class "Default")
      (node (ref "C49") (pin "1") (pinfunction "1_1") (pintype "passive"))
      (node (ref "IC4") (pin "2") (pinfunction "VIN_2") (pintype "bidirectional"))
      (node (ref "R18") (pin "1") (pinfunction "1_1") (pintype "passive"))
      (node (ref "R22") (pin "2") (pinfunction "2_2") (pintype "passive"))
    )
    (net (code "97") (name "Net-(IC4-VOUT+)") (class "Default")
      (node (ref "IC4") (pin "7") (pinfunction "VOUT+_7") (pintype "bidirectional"))
      (node (ref "R23") (pin "1") (pinfunction "1_1") (pintype "passive"))
    )
    (net (code "98") (name "Net-(IC4-VOUT-)") (class "Default")
      (node (ref "IC4") (pin "6") (pinfunction "VOUT-_6") (pintype "bidirectional"))
      (node (ref "R19") (pin "1") (pinfunction "1_1") (pintype "passive"))
    )
    (net (code "99") (name "Net-(IC5-+IN)") (class "Default")
      (node (ref "C62") (pin "1") (pinfunction "1_1") (pintype "passive"))
      (node (ref "IC5") (pin "3") (pinfunction "+IN_3") (pintype "input"))
      (node (ref "R33") (pin "2") (pinfunction "2_2") (pintype "passive"))
      (node (ref "R36") (pin "1") (pinfunction "1_1") (pintype "passive"))
    )
    (net (code "100") (name "Net-(IC5--IN)") (class "Default")
      (node (ref "C55") (pin "2") (pinfunction "2_2") (pintype "passive"))
      (node (ref "IC5") (pin "2") (pinfunction "-IN_2") (pintype "input"))
      (node (ref "R26") (pin "1") (pinfunction "1_1") (pintype "passive"))
      (node (ref "R29") (pin "2") (pinfunction "2_2") (pintype "passive"))
    )
    (net (code "101") (name "Net-(IC6-+IN)") (class "Default")
      (node (ref "C66") (pin "1") (pinfunction "1_1") (pintype "passive"))
      (node (ref "IC6") (pin "3") (pinfunction "+IN_3") (pintype "input"))
      (node (ref "R35") (pin "2") (pinfunction "2_2") (pintype "passive"))
      (node (ref "R37") (pin "1") (pinfunction "1_1") (pintype "passive"))
    )
    (net (code "102") (name "Net-(IC6--IN)") (class "Default")
      (node (ref "C56") (pin "2") (pinfunction "2_2") (pintype "passive"))
      (node (ref "IC6") (pin "2") (pinfunction "-IN_2") (pintype "input"))
      (node (ref "R27") (pin "1") (pinfunction "1_1") (pintype "passive"))
      (node (ref "R31") (pin "2") (pinfunction "2_2") (pintype "passive"))
    )
    (net (code "103") (name "Net-(IC7-VIN)") (class "Default")
      (node (ref "C58") (pin "1") (pinfunction "1_1") (pintype "passive"))
      (node (ref "IC7") (pin "2") (pinfunction "VIN_2") (pintype "bidirectional"))
      (node (ref "R28") (pin "1") (pinfunction "1_1") (pintype "passive"))
      (node (ref "R32") (pin "2") (pinfunction "2_2") (pintype "passive"))
    )
    (net (code "104") (name "Net-(IC7-VOUT+)") (class "Default")
      (node (ref "IC7") (pin "7") (pinfunction "VOUT+_7") (pintype "bidirectional"))
      (node (ref "R33") (pin "1") (pinfunction "1_1") (pintype "passive"))
    )
    (net (code "105") (name "Net-(IC7-VOUT-)") (class "Default")
      (node (ref "IC7") (pin "6") (pinfunction "VOUT-_6") (pintype "bidirectional"))
      (node (ref "R29") (pin "1") (pinfunction "1_1") (pintype "passive"))
    )
    (net (code "106") (name "Net-(IC8-VIN)") (class "Default")
      (node (ref "C63") (pin "1") (pinfunction "1_1") (pintype "passive"))
      (node (ref "IC8") (pin "2") (pinfunction "VIN_2") (pintype "bidirectional"))
      (node (ref "R30") (pin "1") (pinfunction "1_1") (pintype "passive"))
      (node (ref "R34") (pin "2") (pinfunction "2_2") (pintype "passive"))
    )
    (net (code "107") (name "Net-(IC8-VOUT+)") (class "Default")
      (node (ref "IC8") (pin "7") (pinfunction "VOUT+_7") (pintype "bidirectional"))
      (node (ref "R35") (pin "1") (pinfunction "1_1") (pintype "passive"))
    )
    (net (code "108") (name "Net-(IC8-VOUT-)") (class "Default")
      (node (ref "IC8") (pin "6") (pinfunction "VOUT-_6") (pintype "bidirectional"))
      (node (ref "R31") (pin "1") (pinfunction "1_1") (pintype "passive"))
    )
    (net (code "109") (name "Net-(LED-PadA)") (class "Default")
      (node (ref "LED") (pin "A") (pinfunction "A_A") (pintype "passive"))
      (node (ref "R5") (pin "1") (pinfunction "1_1") (pintype "passive"))
    )
    (net (code "110") (name "Net-(OK1A-A)") (class "Default")
      (node (ref "OK1") (pin "1") (pinfunction "A_1") (pintype "passive"))
      (node (ref "R44") (pin "2") (pinfunction "2_2") (pintype "passive"))
    )
    (net (code "111") (name "Net-(OK1A-COL)") (class "Default")
      (node (ref "OK1") (pin "8") (pinfunction "COL_8") (pintype "passive"))
      (node (ref "R45") (pin "1") (pinfunction "1_1") (pintype "passive"))
    )
    (net (code "112") (name "Net-(OK1B-A)") (class "Default")
      (node (ref "OK1") (pin "3") (pinfunction "A_3") (pintype "passive"))
      (node (ref "R46") (pin "2") (pinfunction "2_2") (pintype "passive"))
    )
    (net (code "113") (name "Net-(OK1B-COL)") (class "Default")
      (node (ref "OK1") (pin "6") (pinfunction "COL_6") (pintype "passive"))
      (node (ref "R47") (pin "1") (pinfunction "1_1") (pintype "passive"))
    )
    (net (code "114") (name "Net-(OK2A-A)") (class "Default")
      (node (ref "OK2") (pin "1") (pinfunction "A_1") (pintype "passive"))
      (node (ref "R50") (pin "2") (pinfunction "2_2") (pintype "passive"))
    )
    (net (code "115") (name "Net-(OK2A-COL)") (class "Default")
      (node (ref "OK2") (pin "8") (pinfunction "COL_8") (pintype "passive"))
      (node (ref "R51") (pin "1") (pinfunction "1_1") (pintype "passive"))
    )
    (net (code "116") (name "Net-(OK2B-A)") (class "Default")
      (node (ref "OK2") (pin "3") (pinfunction "A_3") (pintype "passive"))
      (node (ref "R52") (pin "2") (pinfunction "2_2") (pintype "passive"))
    )
    (net (code "117") (name "Net-(OK2B-COL)") (class "Default")
      (node (ref "OK2") (pin "6") (pinfunction "COL_6") (pintype "passive"))
      (node (ref "R53") (pin "1") (pinfunction "1_1") (pintype "passive"))
    )
    (net (code "118") (name "Net-(PTC-2)") (class "Default")
      (node (ref "D9") (pin "C") (pinfunction "C_C") (pintype "passive"))
      (node (ref "PTC") (pin "P$2") (pinfunction "2_P$2") (pintype "passive"))
      (node (ref "TVS") (pin "C") (pinfunction "C_C") (pintype "passive"))
      (node (ref "ZEN") (pin "C") (pinfunction "C_C") (pintype "passive"))
    )
    (net (code "119") (name "Net-(R38-Pad2)") (class "Default")
      (node (ref "R38") (pin "2") (pinfunction "2_2") (pintype "passive"))
      (node (ref "SJ1") (pin "2") (pinfunction "2_2") (pintype "passive"))
    )
    (net (code "120") (name "Net-(R39-Pad2)") (class "Default")
      (node (ref "R39") (pin "2") (pinfunction "2_2") (pintype "passive"))
      (node (ref "SJ2") (pin "2") (pinfunction "2_2") (pintype "passive"))
    )
    (net (code "121") (name "Net-(R40-Pad2)") (class "Default")
      (node (ref "R40") (pin "2") (pinfunction "2_2") (pintype "passive"))
      (node (ref "SJ3") (pin "2") (pinfunction "2_2") (pintype "passive"))
    )
    (net (code "122") (name "Net-(R41-Pad2)") (class "Default")
      (node (ref "R41") (pin "2") (pinfunction "2_2") (pintype "passive"))
      (node (ref "SJ4") (pin "2") (pinfunction "2_2") (pintype "passive"))
    )
    (net (code "123") (name "Net-(U$1-CTS0)") (class "Default")
      (node (ref "U$1") (pin "P5") (pinfunction "CTS0_P5") (pintype "bidirectional"))
      (node (ref "U$1") (pin "P6") (pinfunction "RTS0_P6") (pintype "bidirectional"))
    )
    (net (code "124") (name "Net-(U$1-RF_LED)") (class "Default")
      (node (ref "U$1") (pin "P10") (pinfunction "RF_LED_P10") (pintype "bidirectional"))
      (node (ref "WIFI") (pin "C") (pinfunction "C_C") (pintype "passive"))
    )
    (net (code "125") (name "Net-(U1-DFSDM)") (class "Default")
      (node (ref "R2") (pin "2") (pinfunction "2_2") (pintype "passive"))
      (node (ref "U1") (pin "43") (pinfunction "DFSDM_43") (pintype "input"))
    )
    (net (code "126") (name "Net-(U1-DFSDP)") (class "Default")
      (node (ref "R3") (pin "2") (pinfunction "2_2") (pintype "passive"))
      (node (ref "U1") (pin "42") (pinfunction "DFSDP_42") (pintype "input"))
    )
    (net (code "127") (name "Net-(U1-FWUP)") (class "Default")
      (node (ref "R1") (pin "1") (pinfunction "1_1") (pintype "passive"))
      (node (ref "U1") (pin "53") (pinfunction "FWUP_53") (pintype "input"))
    )
    (net (code "128") (name "unconnected-(IC1-NC-Pad8)") (class "Default")
      (node (ref "IC1") (pin "8") (pinfunction "NC_8") (pintype "no_connect"))
    )
    (net (code "129") (name "unconnected-(IC1-REF-Pad1)") (class "Default")
      (node (ref "IC1") (pin "1") (pinfunction "REF_1") (pintype "passive"))
    )
    (net (code "130") (name "unconnected-(IC1-SENSE-Pad5)") (class "Default")
      (node (ref "IC1") (pin "5") (pinfunction "SENSE_5") (pintype "passive"))
    )
    (net (code "131") (name "unconnected-(IC2-NC-Pad8)") (class "Default")
      (node (ref "IC2") (pin "8") (pinfunction "NC_8") (pintype "no_connect"))
    )
    (net (code "132") (name "unconnected-(IC2-REF-Pad1)") (class "Default")
      (node (ref "IC2") (pin "1") (pinfunction "REF_1") (pintype "passive"))
    )
    (net (code "133") (name "unconnected-(IC2-SENSE-Pad5)") (class "Default")
      (node (ref "IC2") (pin "5") (pinfunction "SENSE_5") (pintype "passive"))
    )
    (net (code "134") (name "unconnected-(IC5-NC-Pad8)") (class "Default")
      (node (ref "IC5") (pin "8") (pinfunction "NC_8") (pintype "no_connect"))
    )
    (net (code "135") (name "unconnected-(IC5-REF-Pad1)") (class "Default")
      (node (ref "IC5") (pin "1") (pinfunction "REF_1") (pintype "passive"))
    )
    (net (code "136") (name "unconnected-(IC5-SENSE-Pad5)") (class "Default")
      (node (ref "IC5") (pin "5") (pinfunction "SENSE_5") (pintype "passive"))
    )
    (net (code "137") (name "unconnected-(IC6-NC-Pad8)") (class "Default")
      (node (ref "IC6") (pin "8") (pinfunction "NC_8") (pintype "no_connect"))
    )
    (net (code "138") (name "unconnected-(IC6-REF-Pad1)") (class "Default")
      (node (ref "IC6") (pin "1") (pinfunction "REF_1") (pintype "passive"))
    )
    (net (code "139") (name "unconnected-(IC6-SENSE-Pad5)") (class "Default")
      (node (ref "IC6") (pin "5") (pinfunction "SENSE_5") (pintype "passive"))
    )
    (net (code "140") (name "unconnected-(IC9-NC-Pad4)") (class "Default")
      (node (ref "IC9") (pin "4") (pinfunction "NC_4") (pintype "input"))
    )
    (net (code "141") (name "unconnected-(IC9-NC-Pad5)") (class "Default")
      (node (ref "IC9") (pin "5") (pinfunction "NC_5") (pintype "input"))
    )
    (net (code "142") (name "unconnected-(IC9-NC-Pad11)") (class "Default")
      (node (ref "IC9") (pin "11") (pinfunction "NC_11") (pintype "input"))
    )
    (net (code "143") (name "unconnected-(IC9-NC-Pad14)") (class "Default")
      (node (ref "IC9") (pin "14") (pinfunction "NC_14") (pintype "input"))
    )
    (net (code "144") (name "unconnected-(IC10-NC-Pad4)") (class "Default")
      (node (ref "IC10") (pin "4") (pinfunction "NC_4") (pintype "input"))
    )
    (net (code "145") (name "unconnected-(IC10-NC-Pad5)") (class "Default")
      (node (ref "IC10") (pin "5") (pinfunction "NC_5") (pintype "input"))
    )
    (net (code "146") (name "unconnected-(IC10-NC-Pad11)") (class "Default")
      (node (ref "IC10") (pin "11") (pinfunction "NC_11") (pintype "input"))
    )
    (net (code "147") (name "unconnected-(IC10-NC-Pad14)") (class "Default")
      (node (ref "IC10") (pin "14") (pinfunction "NC_14") (pintype "input"))
    )
    (net (code "148") (name "unconnected-(U$1-CRSDV-PadP23)") (class "Default")
      (node (ref "U$1") (pin "P23") (pinfunction "CRSDV_P23") (pintype "bidirectional"))
    )
    (net (code "149") (name "unconnected-(U$1-DATA_RDY-PadP7)") (class "Default")
      (node (ref "U$1") (pin "P7") (pinfunction "DATA_RDY_P7") (pintype "bidirectional"))
    )
    (net (code "150") (name "unconnected-(U$1-DDM-PadP18)") (class "Default")
      (node (ref "U$1") (pin "P18") (pinfunction "DDM_P18") (pintype "bidirectional"))
    )
    (net (code "151") (name "unconnected-(U$1-DDP-PadP17)") (class "Default")
      (node (ref "U$1") (pin "P17") (pinfunction "DDP_P17") (pintype "bidirectional"))
    )
    (net (code "152") (name "unconnected-(U$1-EMDC-PadP26)") (class "Default")
      (node (ref "U$1") (pin "P26") (pinfunction "EMDC_P26") (pintype "bidirectional"))
    )
    (net (code "153") (name "unconnected-(U$1-EMDIO-PadP25)") (class "Default")
      (node (ref "U$1") (pin "P25") (pinfunction "EMDIO_P25") (pintype "bidirectional"))
    )
    (net (code "154") (name "unconnected-(U$1-ERX0-PadP30)") (class "Default")
      (node (ref "U$1") (pin "P30") (pinfunction "ERX0_P30") (pintype "bidirectional"))
    )
    (net (code "155") (name "unconnected-(U$1-ERX1-PadP28)") (class "Default")
      (node (ref "U$1") (pin "P28") (pinfunction "ERX1_P28") (pintype "bidirectional"))
    )
    (net (code "156") (name "unconnected-(U$1-ERXER-PadP24)") (class "Default")
      (node (ref "U$1") (pin "P24") (pinfunction "ERXER_P24") (pintype "bidirectional"))
    )
    (net (code "157") (name "unconnected-(U$1-ETX0-PadP29)") (class "Default")
      (node (ref "U$1") (pin "P29") (pinfunction "ETX0_P29") (pintype "bidirectional"))
    )
    (net (code "158") (name "unconnected-(U$1-ETX1-PadP27)") (class "Default")
      (node (ref "U$1") (pin "P27") (pinfunction "ETX1_P27") (pintype "bidirectional"))
    )
    (net (code "159") (name "unconnected-(U$1-ETX_EN-PadP21)") (class "Default")
      (node (ref "U$1") (pin "P21") (pinfunction "ETX_EN_P21") (pintype "bidirectional"))
    )
    (net (code "160") (name "unconnected-(U$1-GND2-PadP20)") (class "Default")
      (node (ref "U$1") (pin "P20") (pinfunction "GND2_P20") (pintype "bidirectional"))
    )
    (net (code "161") (name "unconnected-(U$1-NC-PadP19)") (class "Default")
      (node (ref "U$1") (pin "P19") (pinfunction "NC_P19") (pintype "bidirectional"))
    )
    (net (code "162") (name "unconnected-(U$1-READY-PadP16)") (class "Default")
      (node (ref "U$1") (pin "P16") (pinfunction "READY_P16") (pintype "bidirectional"))
    )
    (net (code "163") (name "unconnected-(U$1-RMII_RCLK-PadP22)") (class "Default")
      (node (ref "U$1") (pin "P22") (pinfunction "RMII_RCLK_P22") (pintype "bidirectional"))
    )
    (net (code "164") (name "unconnected-(U$1-SPI1_CLK-PadP12)") (class "Default")
      (node (ref "U$1") (pin "P12") (pinfunction "SPI1_CLK_P12") (pintype "bidirectional"))
    )
    (net (code "165") (name "unconnected-(U$1-SPI1_CS-PadP11)") (class "Default")
      (node (ref "U$1") (pin "P11") (pinfunction "SPI1_CS_P11") (pintype "bidirectional"))
    )
    (net (code "166") (name "unconnected-(U$1-SPI1_INT-PadP15)") (class "Default")
      (node (ref "U$1") (pin "P15") (pinfunction "SPI1_INT_P15") (pintype "bidirectional"))
    )
    (net (code "167") (name "unconnected-(U$1-SPI1_MISO-PadP13)") (class "Default")
      (node (ref "U$1") (pin "P13") (pinfunction "SPI1_MISO_P13") (pintype "bidirectional"))
    )
    (net (code "168") (name "unconnected-(U$1-SPI1_MOSI-PadP14)") (class "Default")
      (node (ref "U$1") (pin "P14") (pinfunction "SPI1_MOSI_P14") (pintype "bidirectional"))
    )
    (net (code "169") (name "unconnected-(U1-NRST-Pad69)") (class "Default")
      (node (ref "U1") (pin "69") (pinfunction "NRST_69") (pintype "bidirectional"))
    )
    (net (code "170") (name "unconnected-(U1-PA2-Pad85)") (class "Default")
      (node (ref "U1") (pin "85") (pinfunction "PA2_85") (pintype "bidirectional"))
    )
    (net (code "171") (name "unconnected-(U1-PA3-Pad84)") (class "Default")
      (node (ref "U1") (pin "84") (pinfunction "PA3_84") (pintype "bidirectional"))
    )
    (net (code "172") (name "unconnected-(U1-PA4-Pad83)") (class "Default")
      (node (ref "U1") (pin "83") (pinfunction "PA4_83") (pintype "bidirectional"))
    )
    (net (code "173") (name "unconnected-(U1-PA5-Pad25)") (class "Default")
      (node (ref "U1") (pin "25") (pinfunction "PA5_25") (pintype "bidirectional"))
    )
    (net (code "174") (name "unconnected-(U1-PA6-Pad82)") (class "Default")
      (node (ref "U1") (pin "82") (pinfunction "PA6_82") (pintype "bidirectional"))
    )
    (net (code "175") (name "unconnected-(U1-PA7-Pad26)") (class "Default")
      (node (ref "U1") (pin "26") (pinfunction "PA7_26") (pintype "bidirectional"))
    )
    (net (code "176") (name "unconnected-(U1-PA8-Pad27)") (class "Default")
      (node (ref "U1") (pin "27") (pinfunction "PA8_27") (pintype "bidirectional"))
    )
    (net (code "177") (name "unconnected-(U1-PA9-Pad2)") (class "Default")
      (node (ref "U1") (pin "2") (pinfunction "PA9_2") (pintype "bidirectional"))
    )
    (net (code "178") (name "unconnected-(U1-PA10-Pad3)") (class "Default")
      (node (ref "U1") (pin "3") (pinfunction "PA10_3") (pintype "bidirectional"))
    )
    (net (code "179") (name "unconnected-(U1-PA14-Pad7)") (class "Default")
      (node (ref "U1") (pin "7") (pinfunction "PA14_7") (pintype "bidirectional"))
    )
    (net (code "180") (name "unconnected-(U1-PA15-Pad8)") (class "Default")
      (node (ref "U1") (pin "8") (pinfunction "PA15_8") (pintype "bidirectional"))
    )
    (net (code "181") (name "unconnected-(U1-PA17-Pad9)") (class "Default")
      (node (ref "U1") (pin "9") (pinfunction "PA17_9") (pintype "bidirectional"))
    )
    (net (code "182") (name "unconnected-(U1-PA18-Pad70)") (class "Default")
      (node (ref "U1") (pin "70") (pinfunction "PA18_70") (pintype "bidirectional"))
    )
    (net (code "183") (name "unconnected-(U1-PA20-Pad72)") (class "Default")
      (node (ref "U1") (pin "72") (pinfunction "PA20_72") (pintype "bidirectional"))
    )
    (net (code "184") (name "unconnected-(U1-PA21-Pad107)") (class "Default")
      (node (ref "U1") (pin "107") (pinfunction "PA21_107") (pintype "bidirectional"))
    )
    (net (code "185") (name "unconnected-(U1-PA25-Pad108)") (class "Default")
      (node (ref "U1") (pin "108") (pinfunction "PA25_108") (pintype "bidirectional"))
    )
    (net (code "186") (name "unconnected-(U1-PA26-Pad109)") (class "Default")
      (node (ref "U1") (pin "109") (pinfunction "PA26_109") (pintype "bidirectional"))
    )
    (net (code "187") (name "unconnected-(U1-PA27-Pad110)") (class "Default")
      (node (ref "U1") (pin "110") (pinfunction "PA27_110") (pintype "bidirectional"))
    )
    (net (code "188") (name "unconnected-(U1-PA28-Pad111)") (class "Default")
      (node (ref "U1") (pin "111") (pinfunction "PA28_111") (pintype "bidirectional"))
    )
    (net (code "189") (name "unconnected-(U1-PA29-Pad112)") (class "Default")
      (node (ref "U1") (pin "112") (pinfunction "PA29_112") (pintype "bidirectional"))
    )
    (net (code "190") (name "unconnected-(U1-PB0-Pad113)") (class "Default")
      (node (ref "U1") (pin "113") (pinfunction "PB0_113") (pintype "bidirectional"))
    )
    (net (code "191") (name "unconnected-(U1-PB1-Pad114)") (class "Default")
      (node (ref "U1") (pin "114") (pinfunction "PB1_114") (pintype "bidirectional"))
    )
    (net (code "192") (name "unconnected-(U1-PB2-Pad115)") (class "Default")
      (node (ref "U1") (pin "115") (pinfunction "PB2_115") (pintype "bidirectional"))
    )
    (net (code "193") (name "unconnected-(U1-PB3-Pad118)") (class "Default")
      (node (ref "U1") (pin "118") (pinfunction "PB3_118") (pintype "bidirectional"))
    )
    (net (code "194") (name "unconnected-(U1-PB4-Pad119)") (class "Default")
      (node (ref "U1") (pin "119") (pinfunction "PB4_119") (pintype "bidirectional"))
    )
    (net (code "195") (name "unconnected-(U1-PB5-Pad120)") (class "Default")
      (node (ref "U1") (pin "120") (pinfunction "PB5_120") (pintype "bidirectional"))
    )
    (net (code "196") (name "unconnected-(U1-PB6-Pad121)") (class "Default")
      (node (ref "U1") (pin "121") (pinfunction "PB6_121") (pintype "bidirectional"))
    )
    (net (code "197") (name "unconnected-(U1-PB7-Pad122)") (class "Default")
      (node (ref "U1") (pin "122") (pinfunction "PB7_122") (pintype "bidirectional"))
    )
    (net (code "198") (name "unconnected-(U1-PB8-Pad123)") (class "Default")
      (node (ref "U1") (pin "123") (pinfunction "PB8_123") (pintype "bidirectional"))
    )
    (net (code "199") (name "unconnected-(U1-PB9-Pad127)") (class "Default")
      (node (ref "U1") (pin "127") (pinfunction "PB9_127") (pintype "bidirectional"))
    )
    (net (code "200") (name "unconnected-(U1-PB10-Pad128)") (class "Default")
      (node (ref "U1") (pin "128") (pinfunction "PB10_128") (pintype "bidirectional"))
    )
    (net (code "201") (name "unconnected-(U1-PB11-Pad129)") (class "Default")
      (node (ref "U1") (pin "129") (pinfunction "PB11_129") (pintype "bidirectional"))
    )
    (net (code "202") (name "unconnected-(U1-PB16-Pad77)") (class "Default")
      (node (ref "U1") (pin "77") (pinfunction "PB16_77") (pintype "bidirectional"))
    )
    (net (code "203") (name "unconnected-(U1-PB18-Pad89)") (class "Default")
      (node (ref "U1") (pin "89") (pinfunction "PB18_89") (pintype "bidirectional"))
    )
    (net (code "204") (name "unconnected-(U1-PB22-Pad141)") (class "Default")
      (node (ref "U1") (pin "141") (pinfunction "PB22_141") (pintype "bidirectional"))
    )
    (net (code "205") (name "unconnected-(U1-PB23-Pad142)") (class "Default")
      (node (ref "U1") (pin "142") (pinfunction "PB23_142") (pintype "bidirectional"))
    )
    (net (code "206") (name "unconnected-(U1-PB24-Pad143)") (class "Default")
      (node (ref "U1") (pin "143") (pinfunction "PB24_143") (pintype "bidirectional"))
    )
    (net (code "207") (name "unconnected-(U1-PB26-Pad1)") (class "Default")
      (node (ref "U1") (pin "1") (pinfunction "PB26_1") (pintype "bidirectional"))
    )
    (net (code "208") (name "unconnected-(U1-PB28-Pad28)") (class "Default")
      (node (ref "U1") (pin "28") (pinfunction "PB28_28") (pintype "bidirectional"))
    )
    (net (code "209") (name "unconnected-(U1-PB29-Pad29)") (class "Default")
      (node (ref "U1") (pin "29") (pinfunction "PB29_29") (pintype "bidirectional"))
    )
    (net (code "210") (name "unconnected-(U1-PB30-Pad30)") (class "Default")
      (node (ref "U1") (pin "30") (pinfunction "PB30_30") (pintype "bidirectional"))
    )
    (net (code "211") (name "unconnected-(U1-PB31-Pad31)") (class "Default")
      (node (ref "U1") (pin "31") (pinfunction "PB31_31") (pintype "bidirectional"))
    )
    (net (code "212") (name "unconnected-(U1-PC1-Pad55)") (class "Default")
      (node (ref "U1") (pin "55") (pinfunction "PC1_55") (pintype "bidirectional"))
    )
    (net (code "213") (name "unconnected-(U1-PC2-Pad59)") (class "Default")
      (node (ref "U1") (pin "59") (pinfunction "PC2_59") (pintype "bidirectional"))
    )
    (net (code "214") (name "unconnected-(U1-PC3-Pad60)") (class "Default")
      (node (ref "U1") (pin "60") (pinfunction "PC3_60") (pintype "bidirectional"))
    )
    (net (code "215") (name "unconnected-(U1-PC4-Pad116)") (class "Default")
      (node (ref "U1") (pin "116") (pinfunction "PC4_116") (pintype "bidirectional"))
    )
    (net (code "216") (name "unconnected-(U1-PC5-Pad63)") (class "Default")
      (node (ref "U1") (pin "63") (pinfunction "PC5_63") (pintype "bidirectional"))
    )
    (net (code "217") (name "unconnected-(U1-PC6-Pad64)") (class "Default")
      (node (ref "U1") (pin "64") (pinfunction "PC6_64") (pintype "bidirectional"))
    )
    (net (code "218") (name "unconnected-(U1-PC7-Pad65)") (class "Default")
      (node (ref "U1") (pin "65") (pinfunction "PC7_65") (pintype "bidirectional"))
    )
    (net (code "219") (name "unconnected-(U1-PC8-Pad66)") (class "Default")
      (node (ref "U1") (pin "66") (pinfunction "PC8_66") (pintype "bidirectional"))
    )
    (net (code "220") (name "unconnected-(U1-PC9-Pad67)") (class "Default")
      (node (ref "U1") (pin "67") (pinfunction "PC9_67") (pintype "bidirectional"))
    )
    (net (code "221") (name "unconnected-(U1-PC10-Pad117)") (class "Default")
      (node (ref "U1") (pin "117") (pinfunction "PC10_117") (pintype "bidirectional"))
    )
    (net (code "222") (name "unconnected-(U1-PC16-Pad98)") (class "Default")
      (node (ref "U1") (pin "98") (pinfunction "PC16_98") (pintype "bidirectional"))
    )
    (net (code "223") (name "unconnected-(U1-PC17-Pad99)") (class "Default")
      (node (ref "U1") (pin "99") (pinfunction "PC17_99") (pintype "bidirectional"))
    )
    (net (code "224") (name "unconnected-(U1-PC18-Pad100)") (class "Default")
      (node (ref "U1") (pin "100") (pinfunction "PC18_100") (pintype "bidirectional"))
    )
    (net (code "225") (name "unconnected-(U1-PC19-Pad101)") (class "Default")
      (node (ref "U1") (pin "101") (pinfunction "PC19_101") (pintype "bidirectional"))
    )
    (net (code "226") (name "unconnected-(U1-PC20-Pad131)") (class "Default")
      (node (ref "U1") (pin "131") (pinfunction "PC20_131") (pintype "bidirectional"))
    )
    (net (code "227") (name "unconnected-(U1-PC27-Pad138)") (class "Default")
      (node (ref "U1") (pin "138") (pinfunction "PC27_138") (pintype "bidirectional"))
    )
    (net (code "228") (name "unconnected-(U1-PC29-Pad102)") (class "Default")
      (node (ref "U1") (pin "102") (pinfunction "PC29_102") (pintype "bidirectional"))
    )
    (net (code "229") (name "unconnected-(U1-PC30-Pad103)") (class "Default")
      (node (ref "U1") (pin "103") (pinfunction "PC30_103") (pintype "bidirectional"))
    )
    (net (code "230") (name "unconnected-(U1-PD0-Pad13)") (class "Default")
      (node (ref "U1") (pin "13") (pinfunction "PD0_13") (pintype "bidirectional"))
    )
    (net (code "231") (name "unconnected-(U1-PD1-Pad14)") (class "Default")
      (node (ref "U1") (pin "14") (pinfunction "PD1_14") (pintype "bidirectional"))
    )
    (net (code "232") (name "unconnected-(U1-PD2-Pad15)") (class "Default")
      (node (ref "U1") (pin "15") (pinfunction "PD2_15") (pintype "bidirectional"))
    )
    (net (code "233") (name "unconnected-(U1-PD3-Pad16)") (class "Default")
      (node (ref "U1") (pin "16") (pinfunction "PD3_16") (pintype "bidirectional"))
    )
    (net (code "234") (name "unconnected-(U1-PD6-Pad19)") (class "Default")
      (node (ref "U1") (pin "19") (pinfunction "PD6_19") (pintype "bidirectional"))
    )
    (net (code "235") (name "unconnected-(U1-PD7-Pad20)") (class "Default")
      (node (ref "U1") (pin "20") (pinfunction "PD7_20") (pintype "bidirectional"))
    )
    (net (code "236") (name "unconnected-(U1-PD8-Pad21)") (class "Default")
      (node (ref "U1") (pin "21") (pinfunction "PD8_21") (pintype "bidirectional"))
    )
    (net (code "237") (name "unconnected-(U1-PD9-Pad22)") (class "Default")
      (node (ref "U1") (pin "22") (pinfunction "PD9_22") (pintype "bidirectional"))
    )
    (net (code "238") (name "unconnected-(U1-PD10-Pad32)") (class "Default")
      (node (ref "U1") (pin "32") (pinfunction "PD10_32") (pintype "bidirectional"))
    )
    (net (code "239") (name "unconnected-(U1-SHDN-Pad50)") (class "Default")
      (node (ref "U1") (pin "50") (pinfunction "SHDN_50") (pintype "output"))
    )
    (net (code "240") (name "unconnected-(U1-TST-Pad51)") (class "Default")
      (node (ref "U1") (pin "51") (pinfunction "TST_51") (pintype "input"))
    )
    (net (code "241") (name "unconnected-(U7-WC-PadPIN7)") (class "Default")
      (node (ref "U7") (pin "PIN7") (pinfunction "WC_PIN7") (pintype "bidirectional"))
    )
    (net (code "242") (name "unconnected-(X1-PadS1)") (class "Default")
      (node (ref "X1") (pin "S1") (pinfunction "S1_S1") (pintype "passive"))
    )
    (net (code "243") (name "unconnected-(X1-PadS2)") (class "Default")
      (node (ref "X1") (pin "S2") (pinfunction "S2_S2") (pintype "passive"))
    )
  )
)
